# SCH_PCB_Schematic_2021-12-08.net
KiCad netlist of a schematic drawn in EasyEDA
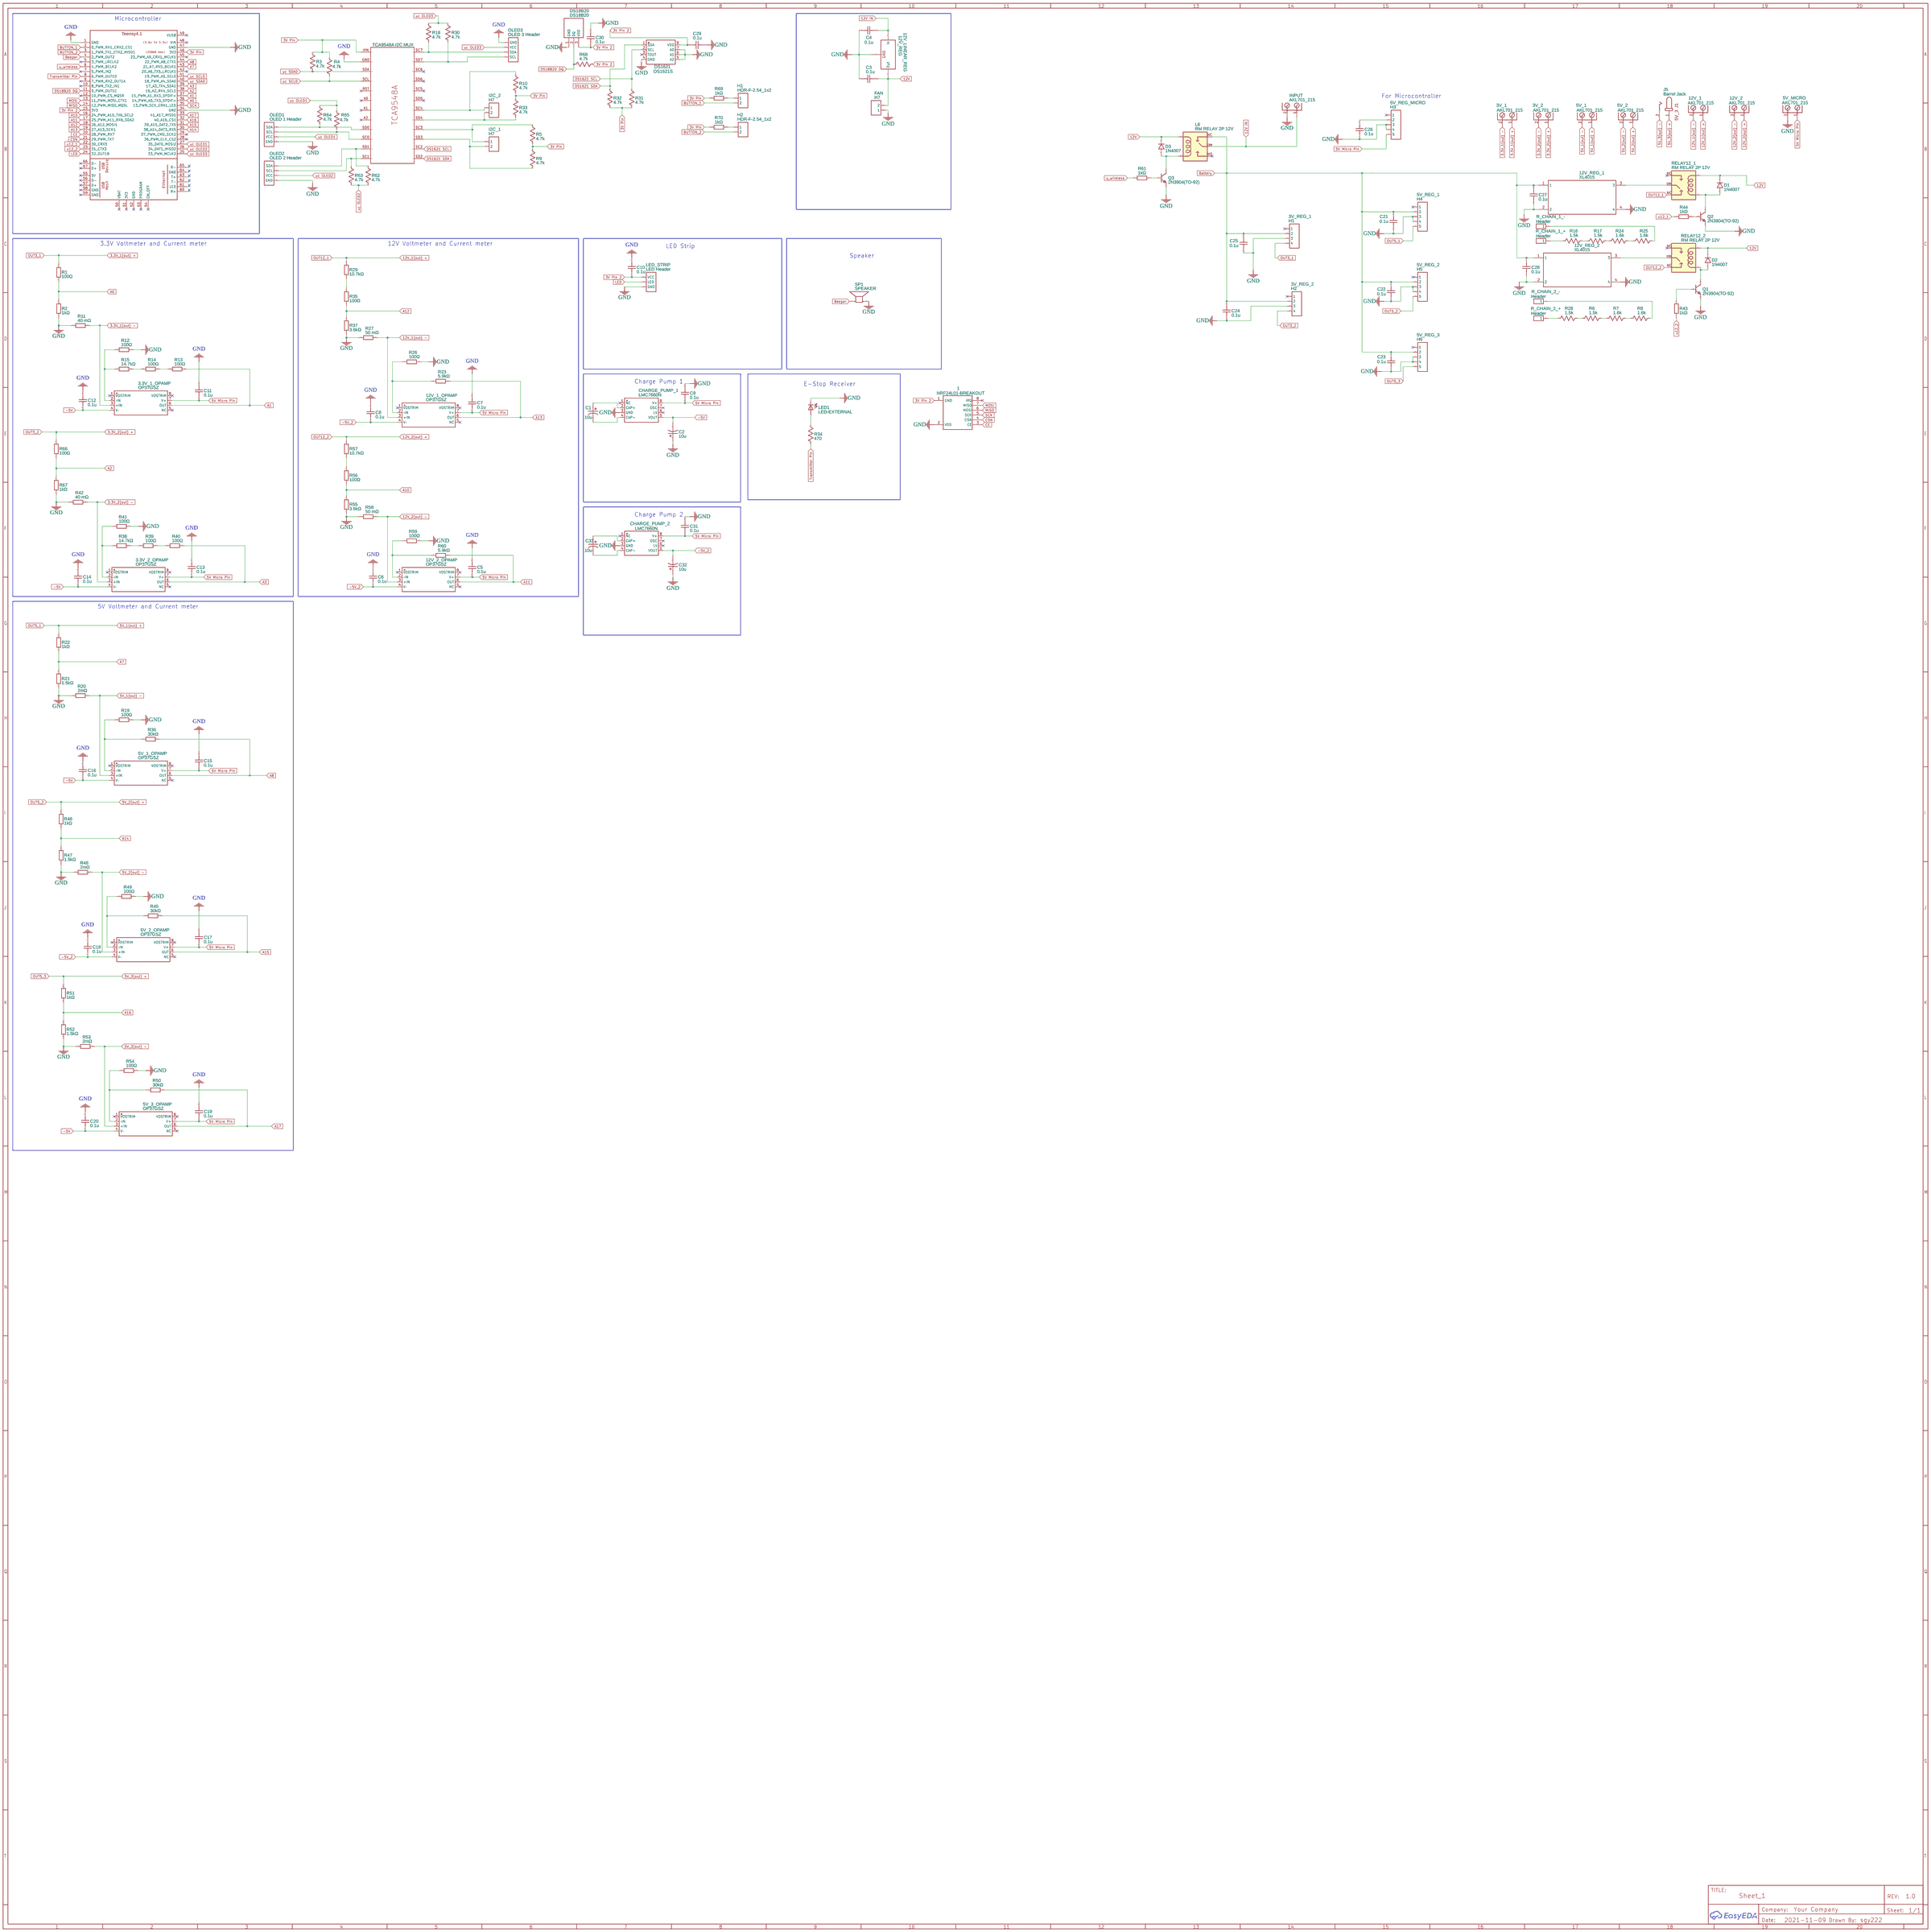
[diagram p0: schematic sheet]

(export (version "E")
  (design (tool "Eeschema 10.0.6"))
  (components
    (comp (ref "1") (value "NRF24L01-BREAKOUT") (libsource (lib "") (part "NRF24L01-BREAKOUT")))
    (comp (ref "3.3V_1_OPAMP")
      (value "OP37GSZ")
      (fields (field (name "BOM_Supplier Part") "C690944"))
      (libsource (lib "") (part "OP37GSZ_1"))
    )
    (comp (ref "3.3V_2_OPAMP")
      (value "OP37GSZ")
      (fields (field (name "BOM_Supplier Part") "C690944"))
      (libsource (lib "") (part "OP37GSZ_2"))
    )
    (comp (ref "3V_1") (value "AKL701_215") (libsource (lib "") (part "AKL701_215_1")))
    (comp (ref "3V_2") (value "AKL701_215") (libsource (lib "") (part "AKL701_215_1")))
    (comp (ref "3V_REG_1")
      (value "H1")
      (fields (field (name "BOM_Supplier Part") "C225501"))
      (libsource (lib "") (part "HDR-F-2.54_1x4"))
    )
    (comp (ref "3V_REG_2")
      (value "H2")
      (fields (field (name "BOM_Supplier Part") "C225501"))
      (libsource (lib "") (part "HDR-F-2.54_1x4"))
    )
    (comp (ref "5V_1") (value "AKL701_215") (libsource (lib "") (part "AKL701_215")))
    (comp (ref "5V_1_OPAMP")
      (value "OP37GSZ")
      (fields (field (name "BOM_Supplier Part") "C690944"))
      (libsource (lib "") (part "OP37GSZ"))
    )
    (comp (ref "5V_2") (value "AKL701_215") (libsource (lib "") (part "AKL701_215")))
    (comp (ref "5V_2_OPAMP")
      (value "OP37GSZ")
      (fields (field (name "BOM_Supplier Part") "C690944"))
      (libsource (lib "") (part "OP37GSZ_4"))
    )
    (comp (ref "5V_3_OPAMP")
      (value "OP37GSZ")
      (fields (field (name "BOM_Supplier Part") "C690944"))
      (libsource (lib "") (part "OP37GSZ_3"))
    )
    (comp (ref "5V_MICRO") (value "AKL701_215") (libsource (lib "") (part "AKL701_215_3")))
    (comp (ref "5V_REG_1")
      (value "H4")
      (fields (field (name "BOM_Supplier Part") "C50950"))
      (libsource (lib "") (part "HDR-F-2.54_1x5_1"))
    )
    (comp (ref "5V_REG_2")
      (value "H5")
      (fields (field (name "BOM_Supplier Part") "C50950"))
      (libsource (lib "") (part "HDR-F-2.54_1x5_1"))
    )
    (comp (ref "5V_REG_3")
      (value "H6")
      (fields (field (name "BOM_Supplier Part") "C50950"))
      (libsource (lib "") (part "HDR-F-2.54_1x5_1"))
    )
    (comp (ref "5V_REG_MICRO")
      (value "H3")
      (fields (field (name "BOM_Supplier Part") "C50950"))
      (libsource (lib "") (part "HDR-F-2.54_1x5"))
    )
    (comp (ref "12V_1") (value "AKL701_215") (libsource (lib "") (part "AKL701_215_2")))
    (comp (ref "12V_1_OPAMP")
      (value "OP37GSZ")
      (fields (field (name "BOM_Supplier Part") "C690944"))
      (libsource (lib "") (part "OP37GSZ_5"))
    )
    (comp (ref "12V_2") (value "AKL701_215") (libsource (lib "") (part "AKL701_215_2")))
    (comp (ref "12V_2_OPAMP")
      (value "OP37GSZ")
      (fields (field (name "BOM_Supplier Part") "C690944"))
      (libsource (lib "") (part "OP37GSZ_6"))
    )
    (comp (ref "12V_REG")
      (value "12V_LINEAR_REG")
      (fields (field (name "BOM_Manufacturer Part") "VoltageRegulator-xxV"))
      (libsource (lib "") (part "VoltageRegulator-xxV"))
    )
    (comp (ref "12V_REG_1") (value "XL4015") (libsource (lib "") (part "XL4015")))
    (comp (ref "12V_REG_2") (value "XL4015") (libsource (lib "") (part "XL4015")))
    (comp (ref "C1") (value "10u") (libsource (lib "") (part "CE_TH_D5.0×F2.0_US_2")))
    (comp (ref "C2") (value "10u") (libsource (lib "") (part "CE_TH_D5.0×F2.0_US_1")))
    (comp (ref "C3") (value "0.1u") (libsource (lib "") (part "C_0603_US_1")))
    (comp (ref "C4") (value "0.1u") (libsource (lib "") (part "C_0603_US_1")))
    (comp (ref "C5") (value "0.1u") (libsource (lib "") (part "C_0603_US")))
    (comp (ref "C6") (value "0.1u") (libsource (lib "") (part "C_0603_US_2")))
    (comp (ref "C7") (value "0.1u") (libsource (lib "") (part "C_0603_US")))
    (comp (ref "C8") (value "0.1u") (libsource (lib "") (part "C_0603_US")))
    (comp (ref "C9") (value "0.1u") (libsource (lib "") (part "C_0603_US")))
    (comp (ref "C10") (value "0.1u") (libsource (lib "") (part "C_0603_US")))
    (comp (ref "C11") (value "0.1u") (libsource (lib "") (part "C_0603_US")))
    (comp (ref "C12") (value "0.1u") (libsource (lib "") (part "C_0603_US")))
    (comp (ref "C13") (value "0.1u") (libsource (lib "") (part "C_0603_US")))
    (comp (ref "C14") (value "0.1u") (libsource (lib "") (part "C_0603_US")))
    (comp (ref "C15") (value "0.1u") (libsource (lib "") (part "C_0603_US")))
    (comp (ref "C16") (value "0.1u") (libsource (lib "") (part "C_0603_US")))
    (comp (ref "C17") (value "0.1u") (libsource (lib "") (part "C_0603_US")))
    (comp (ref "C18") (value "0.1u") (libsource (lib "") (part "C_0603_US")))
    (comp (ref "C19") (value "0.1u") (libsource (lib "") (part "C_0603_US")))
    (comp (ref "C20") (value "0.1u") (libsource (lib "") (part "C_0603_US")))
    (comp (ref "C21") (value "0.1u") (libsource (lib "") (part "C_0603_US")))
    (comp (ref "C22") (value "0.1u") (libsource (lib "") (part "C_0603_US")))
    (comp (ref "C23") (value "0.1u") (libsource (lib "") (part "C_0603_US")))
    (comp (ref "C24") (value "0.1u") (libsource (lib "") (part "C_0603_US")))
    (comp (ref "C25") (value "0.1u") (libsource (lib "") (part "C_0603_US")))
    (comp (ref "C26") (value "0.1u") (libsource (lib "") (part "C_0603_US")))
    (comp (ref "C27") (value "0.1u") (libsource (lib "") (part "C_0603_US")))
    (comp (ref "C28") (value "0.1u") (libsource (lib "") (part "C_0603_US")))
    (comp (ref "C29") (value "0.1u") (libsource (lib "") (part "C_0603_US_3")))
    (comp (ref "C30") (value "0.1u") (libsource (lib "") (part "C_0603_US_2")))
    (comp (ref "C31") (value "0.1u") (libsource (lib "") (part "C_0603_US")))
    (comp (ref "C32") (value "10u") (libsource (lib "") (part "CE_TH_D5.0×F2.0_US")))
    (comp (ref "C33") (value "10u") (libsource (lib "") (part "CE_TH_D5.0×F2.0_US_2")))
    (comp (ref "CHARGE_PUMP_1")
      (value "LMC7660N")
      (fields (field (name "BOM_Supplier Part") "C512764"))
      (libsource (lib "") (part "LMC7660N"))
    )
    (comp (ref "CHARGE_PUMP_2")
      (value "LMC7660N")
      (fields (field (name "BOM_Supplier Part") "C512764"))
      (libsource (lib "") (part "LMC7660N"))
    )
    (comp (ref "D1")
      (value "1N4007")
      (fields (field (name "BOM_Supplier Part") "C106903"))
      (libsource (lib "") (part "1N4007"))
    )
    (comp (ref "D2")
      (value "1N4007")
      (fields (field (name "BOM_Supplier Part") "C106903"))
      (libsource (lib "") (part "1N4007"))
    )
    (comp (ref "D3")
      (value "1N4007")
      (fields (field (name "BOM_Supplier Part") "C106903"))
      (libsource (lib "") (part "1N4007"))
    )
    (comp (ref "DS18B20") (value "DS18B20") (libsource (lib "") (part "DS18B20")))
    (comp (ref "DS1621")
      (value "DS1621S")
      (fields (field (name "BOM_Supplier Part") "C407894"))
      (libsource (lib "") (part "DS1621S"))
    )
    (comp (ref "FAN")
      (value "H7")
      (fields (field (name "BOM_Supplier Part") "C124375"))
      (libsource (lib "") (part "HDR-M-2.54_1x2_1"))
    )
    (comp (ref "H1")
      (value "HDR-F-2.54_1x2")
      (fields (field (name "BOM_Supplier Part") "C49661"))
      (libsource (lib "") (part "HDR-F-2.54_1x2"))
    )
    (comp (ref "H2")
      (value "HDR-F-2.54_1x2")
      (fields (field (name "BOM_Supplier Part") "C49661"))
      (libsource (lib "") (part "HDR-F-2.54_1x2"))
    )
    (comp (ref "I2C_1")
      (value "H7")
      (fields (field (name "BOM_Supplier Part") "C124375"))
      (libsource (lib "") (part "HDR-M-2.54_1x2"))
    )
    (comp (ref "I2C_2")
      (value "H7")
      (fields (field (name "BOM_Supplier Part") "C124375"))
      (libsource (lib "") (part "HDR-M-2.54_1x2"))
    )
    (comp (ref "INPUT") (value "AKL701_215") (libsource (lib "") (part "AKL701_215_4")))
    (comp (ref "J5")
      (value "Barrel Jack")
      (fields (field (name "BOM_Manufacturer Part") "PJ-037AH"))
      (libsource (lib "") (part "PJ-037AH"))
    )
    (comp (ref "L8") (value "RM RELAY 2P 12V") (libsource (lib "") (part "RM RELAY 2P 3.3V_1")))
    (comp (ref "LED1") (value "LED-EXTERNAL") (libsource (lib "") (part "LED-EXTERNAL")))
    (comp (ref "LED_STRIP")
      (value "LED Header")
      (fields (field (name "BOM_Supplier Part") "C180248"))
      (libsource (lib "") (part "HDR-M-2.54_1x3"))
    )
    (comp (ref "OLED1")
      (value "OLED 1 Header")
      (fields (field (name "BOM_Supplier Part") "C124378"))
      (libsource (lib "") (part "HDR-M-2.54_1x4"))
    )
    (comp (ref "OLED2")
      (value "OLED 2 Header")
      (fields (field (name "BOM_Supplier Part") "C124378"))
      (libsource (lib "") (part "HDR-M-2.54_1x4"))
    )
    (comp (ref "OLED3")
      (value "OLED 3 Header")
      (fields (field (name "BOM_Supplier Part") "C124378"))
      (libsource (lib "") (part "HDR-M-2.54_1x4_1"))
    )
    (comp (ref "Q1")
      (value "2N3904(TO-92)")
      (fields (field (name "BOM_Manufacturer Part") "2N3904") (field (name "BOM_Supplier Part") "C118538"))
      (libsource (lib "") (part "2N3904(TO-92)"))
    )
    (comp (ref "Q2")
      (value "2N3904(TO-92)")
      (fields (field (name "BOM_Manufacturer Part") "2N3904") (field (name "BOM_Supplier Part") "C118538"))
      (libsource (lib "") (part "2N3904(TO-92)"))
    )
    (comp (ref "Q3")
      (value "2N3904(TO-92)")
      (fields (field (name "BOM_Manufacturer Part") "2N3904") (field (name "BOM_Supplier Part") "C118538"))
      (libsource (lib "") (part "2N3904(TO-92)"))
    )
    (comp (ref "R1")
      (value "100Ω")
      (fields
        (field (name "BOM_Manufacturer Part") "AECR1206F110RK9")
        (field (name "BOM_Supplier Part") "C352159")
      )
      (libsource (lib "") (part "AECR1206F110RK9_1"))
    )
    (comp (ref "R2")
      (value "1kΩ")
      (fields
        (field (name "BOM_Manufacturer Part") "AECR1206F110RK9")
        (field (name "BOM_Supplier Part") "C352159")
      )
      (libsource (lib "") (part "AECR1206F110RK9_1"))
    )
    (comp (ref "R3") (value "4.7k") (libsource (lib "") (part "R_1206_US")))
    (comp (ref "R4") (value "4.7k") (libsource (lib "") (part "R_1206_US")))
    (comp (ref "R5") (value "4.7k") (libsource (lib "") (part "R_1206_US")))
    (comp (ref "R6") (value "1.5k") (libsource (lib "") (part "R_AXIAL-0.3_US")))
    (comp (ref "R7") (value "1.6k") (libsource (lib "") (part "R_AXIAL-0.3_US")))
    (comp (ref "R8") (value "1.6k") (libsource (lib "") (part "R_AXIAL-0.3_US")))
    (comp (ref "R9") (value "4.7k") (libsource (lib "") (part "R_1206_US_2")))
    (comp (ref "R10") (value "4.7k") (libsource (lib "") (part "R_1206_US")))
    (comp (ref "R11")
      (value "40 mΩ")
      (fields
        (field (name "BOM_Manufacturer Part") "AECR1206F110RK9")
        (field (name "BOM_Supplier Part") "C352159")
      )
      (libsource (lib "") (part "AECR1206F110RK9"))
    )
    (comp (ref "R12")
      (value "100Ω")
      (fields
        (field (name "BOM_Manufacturer Part") "AECR1206F110RK9")
        (field (name "BOM_Supplier Part") "C352159")
      )
      (libsource (lib "") (part "AECR1206F110RK9"))
    )
    (comp (ref "R13")
      (value "100Ω")
      (fields
        (field (name "BOM_Manufacturer Part") "AECR1206F110RK9")
        (field (name "BOM_Supplier Part") "C352159")
      )
      (libsource (lib "") (part "AECR1206F110RK9"))
    )
    (comp (ref "R14")
      (value "100Ω")
      (fields
        (field (name "BOM_Manufacturer Part") "AECR1206F110RK9")
        (field (name "BOM_Supplier Part") "C352159")
      )
      (libsource (lib "") (part "AECR1206F110RK9"))
    )
    (comp (ref "R15")
      (value "14.7kΩ")
      (fields
        (field (name "BOM_Manufacturer Part") "AECR1206F110RK9")
        (field (name "BOM_Supplier Part") "C352159")
      )
      (libsource (lib "") (part "AECR1206F110RK9"))
    )
    (comp (ref "R16") (value "1.5k") (libsource (lib "") (part "R_AXIAL-0.3_US")))
    (comp (ref "R17") (value "1.5k") (libsource (lib "") (part "R_AXIAL-0.3_US")))
    (comp (ref "R18") (value "4.7k") (libsource (lib "") (part "R_1206_US")))
    (comp (ref "R19")
      (value "100Ω")
      (fields
        (field (name "BOM_Manufacturer Part") "AECR1206F110RK9")
        (field (name "BOM_Supplier Part") "C352159")
      )
      (libsource (lib "") (part "AECR1206F110RK9"))
    )
    (comp (ref "R20")
      (value "2mΩ")
      (fields
        (field (name "BOM_Manufacturer Part") "AECR1206F110RK9")
        (field (name "BOM_Supplier Part") "C352159")
      )
      (libsource (lib "") (part "AECR1206F110RK9"))
    )
    (comp (ref "R21")
      (value "1.5kΩ")
      (fields
        (field (name "BOM_Manufacturer Part") "AECR1206F110RK9")
        (field (name "BOM_Supplier Part") "C352159")
      )
      (libsource (lib "") (part "AECR1206F110RK9_1"))
    )
    (comp (ref "R22")
      (value "1kΩ")
      (fields
        (field (name "BOM_Manufacturer Part") "AECR1206F110RK9")
        (field (name "BOM_Supplier Part") "C352159")
      )
      (libsource (lib "") (part "AECR1206F110RK9_1"))
    )
    (comp (ref "R23")
      (value "5.9kΩ")
      (fields
        (field (name "BOM_Manufacturer Part") "AECR1206F110RK9")
        (field (name "BOM_Supplier Part") "C352159")
      )
      (libsource (lib "") (part "AECR1206F110RK9"))
    )
    (comp (ref "R24") (value "1.6k") (libsource (lib "") (part "R_AXIAL-0.3_US")))
    (comp (ref "R25") (value "1.6k") (libsource (lib "") (part "R_AXIAL-0.3_US")))
    (comp (ref "R26")
      (value "100Ω")
      (fields
        (field (name "BOM_Manufacturer Part") "AECR1206F110RK9")
        (field (name "BOM_Supplier Part") "C352159")
      )
      (libsource (lib "") (part "AECR1206F110RK9"))
    )
    (comp (ref "R27")
      (value "50 mΩ")
      (fields
        (field (name "BOM_Manufacturer Part") "AECR1206F110RK9")
        (field (name "BOM_Supplier Part") "C352159")
      )
      (libsource (lib "") (part "AECR1206F110RK9"))
    )
    (comp (ref "R28") (value "1.5k") (libsource (lib "") (part "R_AXIAL-0.3_US")))
    (comp (ref "R29")
      (value "10.7kΩ")
      (fields
        (field (name "BOM_Manufacturer Part") "AECR1206F110RK9")
        (field (name "BOM_Supplier Part") "C352159")
      )
      (libsource (lib "") (part "AECR1206F110RK9_1"))
    )
    (comp (ref "R30") (value "4.7k") (libsource (lib "") (part "R_1206_US")))
    (comp (ref "R31") (value "4.7k") (libsource (lib "") (part "R_1206_US")))
    (comp (ref "R32") (value "4.7k") (libsource (lib "") (part "R_1206_US")))
    (comp (ref "R33") (value "4.7k") (libsource (lib "") (part "R_1206_US")))
    (comp (ref "R34") (value "470") (libsource (lib "") (part "1k 1%")))
    (comp (ref "R35")
      (value "100Ω")
      (fields
        (field (name "BOM_Manufacturer Part") "AECR1206F110RK9")
        (field (name "BOM_Supplier Part") "C352159")
      )
      (libsource (lib "") (part "AECR1206F110RK9_1"))
    )
    (comp (ref "R36")
      (value "30kΩ")
      (fields
        (field (name "BOM_Manufacturer Part") "0603WAF3022T5E")
        (field (name "BOM_Supplier Part") "C246852")
      )
      (libsource (lib "") (part "0603WAF3022T5E"))
    )
    (comp (ref "R37")
      (value "3.6kΩ")
      (fields
        (field (name "BOM_Manufacturer Part") "0603WAF3022T5E")
        (field (name "BOM_Supplier Part") "C246852")
      )
      (libsource (lib "") (part "0603WAF3022T5E_1"))
    )
    (comp (ref "R38")
      (value "14.7kΩ")
      (fields
        (field (name "BOM_Manufacturer Part") "AECR1206F110RK9")
        (field (name "BOM_Supplier Part") "C352159")
      )
      (libsource (lib "") (part "AECR1206F110RK9"))
    )
    (comp (ref "R39")
      (value "100Ω")
      (fields
        (field (name "BOM_Manufacturer Part") "AECR1206F110RK9")
        (field (name "BOM_Supplier Part") "C352159")
      )
      (libsource (lib "") (part "AECR1206F110RK9"))
    )
    (comp (ref "R40")
      (value "100Ω")
      (fields
        (field (name "BOM_Manufacturer Part") "AECR1206F110RK9")
        (field (name "BOM_Supplier Part") "C352159")
      )
      (libsource (lib "") (part "AECR1206F110RK9"))
    )
    (comp (ref "R41")
      (value "100Ω")
      (fields
        (field (name "BOM_Manufacturer Part") "AECR1206F110RK9")
        (field (name "BOM_Supplier Part") "C352159")
      )
      (libsource (lib "") (part "AECR1206F110RK9"))
    )
    (comp (ref "R42")
      (value "40 mΩ")
      (fields
        (field (name "BOM_Manufacturer Part") "AECR1206F110RK9")
        (field (name "BOM_Supplier Part") "C352159")
      )
      (libsource (lib "") (part "AECR1206F110RK9"))
    )
    (comp (ref "R43")
      (value "1kΩ")
      (fields
        (field (name "BOM_Manufacturer Part") "AECR1206F110RK9")
        (field (name "BOM_Supplier Part") "C352159")
      )
      (libsource (lib "") (part "AECR1206F110RK9_1"))
    )
    (comp (ref "R44")
      (value "1kΩ")
      (fields
        (field (name "BOM_Manufacturer Part") "AECR1206F110RK9")
        (field (name "BOM_Supplier Part") "C352159")
      )
      (libsource (lib "") (part "AECR1206F110RK9"))
    )
    (comp (ref "R45")
      (value "30kΩ")
      (fields
        (field (name "BOM_Manufacturer Part") "0603WAF3022T5E")
        (field (name "BOM_Supplier Part") "C246852")
      )
      (libsource (lib "") (part "0603WAF3022T5E"))
    )
    (comp (ref "R46")
      (value "1kΩ")
      (fields
        (field (name "BOM_Manufacturer Part") "AECR1206F110RK9")
        (field (name "BOM_Supplier Part") "C352159")
      )
      (libsource (lib "") (part "AECR1206F110RK9_1"))
    )
    (comp (ref "R47")
      (value "1.5kΩ")
      (fields
        (field (name "BOM_Manufacturer Part") "AECR1206F110RK9")
        (field (name "BOM_Supplier Part") "C352159")
      )
      (libsource (lib "") (part "AECR1206F110RK9_1"))
    )
    (comp (ref "R48")
      (value "2mΩ")
      (fields
        (field (name "BOM_Manufacturer Part") "AECR1206F110RK9")
        (field (name "BOM_Supplier Part") "C352159")
      )
      (libsource (lib "") (part "AECR1206F110RK9"))
    )
    (comp (ref "R49")
      (value "100Ω")
      (fields
        (field (name "BOM_Manufacturer Part") "AECR1206F110RK9")
        (field (name "BOM_Supplier Part") "C352159")
      )
      (libsource (lib "") (part "AECR1206F110RK9"))
    )
    (comp (ref "R50")
      (value "30kΩ")
      (fields
        (field (name "BOM_Manufacturer Part") "0603WAF3022T5E")
        (field (name "BOM_Supplier Part") "C246852")
      )
      (libsource (lib "") (part "0603WAF3022T5E"))
    )
    (comp (ref "R51")
      (value "1kΩ")
      (fields
        (field (name "BOM_Manufacturer Part") "AECR1206F110RK9")
        (field (name "BOM_Supplier Part") "C352159")
      )
      (libsource (lib "") (part "AECR1206F110RK9_1"))
    )
    (comp (ref "R52")
      (value "1.5kΩ")
      (fields
        (field (name "BOM_Manufacturer Part") "AECR1206F110RK9")
        (field (name "BOM_Supplier Part") "C352159")
      )
      (libsource (lib "") (part "AECR1206F110RK9_1"))
    )
    (comp (ref "R53")
      (value "2mΩ")
      (fields
        (field (name "BOM_Manufacturer Part") "AECR1206F110RK9")
        (field (name "BOM_Supplier Part") "C352159")
      )
      (libsource (lib "") (part "AECR1206F110RK9"))
    )
    (comp (ref "R54")
      (value "100Ω")
      (fields
        (field (name "BOM_Manufacturer Part") "AECR1206F110RK9")
        (field (name "BOM_Supplier Part") "C352159")
      )
      (libsource (lib "") (part "AECR1206F110RK9"))
    )
    (comp (ref "R55")
      (value "3.6kΩ")
      (fields
        (field (name "BOM_Manufacturer Part") "0603WAF3022T5E")
        (field (name "BOM_Supplier Part") "C246852")
      )
      (libsource (lib "") (part "0603WAF3022T5E_1"))
    )
    (comp (ref "R56")
      (value "100Ω")
      (fields
        (field (name "BOM_Manufacturer Part") "AECR1206F110RK9")
        (field (name "BOM_Supplier Part") "C352159")
      )
      (libsource (lib "") (part "AECR1206F110RK9_1"))
    )
    (comp (ref "R57")
      (value "10.7kΩ")
      (fields
        (field (name "BOM_Manufacturer Part") "AECR1206F110RK9")
        (field (name "BOM_Supplier Part") "C352159")
      )
      (libsource (lib "") (part "AECR1206F110RK9_1"))
    )
    (comp (ref "R58")
      (value "50 mΩ")
      (fields
        (field (name "BOM_Manufacturer Part") "AECR1206F110RK9")
        (field (name "BOM_Supplier Part") "C352159")
      )
      (libsource (lib "") (part "AECR1206F110RK9"))
    )
    (comp (ref "R59")
      (value "100Ω")
      (fields
        (field (name "BOM_Manufacturer Part") "AECR1206F110RK9")
        (field (name "BOM_Supplier Part") "C352159")
      )
      (libsource (lib "") (part "AECR1206F110RK9"))
    )
    (comp (ref "R60")
      (value "5.9kΩ")
      (fields
        (field (name "BOM_Manufacturer Part") "AECR1206F110RK9")
        (field (name "BOM_Supplier Part") "C352159")
      )
      (libsource (lib "") (part "AECR1206F110RK9"))
    )
    (comp (ref "R61")
      (value "1kΩ")
      (fields
        (field (name "BOM_Manufacturer Part") "AECR1206F110RK9")
        (field (name "BOM_Supplier Part") "C352159")
      )
      (libsource (lib "") (part "AECR1206F110RK9_2"))
    )
    (comp (ref "R62") (value "4.7k") (libsource (lib "") (part "R_1206_US_2")))
    (comp (ref "R63") (value "4.7k") (libsource (lib "") (part "R_1206_US")))
    (comp (ref "R64") (value "4.7k") (libsource (lib "") (part "R_1206_US")))
    (comp (ref "R65") (value "4.7k") (libsource (lib "") (part "R_1206_US")))
    (comp (ref "R66")
      (value "100Ω")
      (fields
        (field (name "BOM_Manufacturer Part") "AECR1206F110RK9")
        (field (name "BOM_Supplier Part") "C352159")
      )
      (libsource (lib "") (part "AECR1206F110RK9_1"))
    )
    (comp (ref "R67")
      (value "1kΩ")
      (fields
        (field (name "BOM_Manufacturer Part") "AECR1206F110RK9")
        (field (name "BOM_Supplier Part") "C352159")
      )
      (libsource (lib "") (part "AECR1206F110RK9_1"))
    )
    (comp (ref "R68") (value "4.7k") (libsource (lib "") (part "R_1206_US_1")))
    (comp (ref "R69")
      (value "1kΩ")
      (fields
        (field (name "BOM_Manufacturer Part") "AECR1206F110RK9")
        (field (name "BOM_Supplier Part") "C352159")
      )
      (libsource (lib "") (part "AECR1206F110RK9_2"))
    )
    (comp (ref "R70")
      (value "1kΩ")
      (fields
        (field (name "BOM_Manufacturer Part") "AECR1206F110RK9")
        (field (name "BOM_Supplier Part") "C352159")
      )
      (libsource (lib "") (part "AECR1206F110RK9_2"))
    )
    (comp (ref "RELAY12_1") (value "RM RELAY 2P 12V") (libsource (lib "") (part "RM RELAY 2P 3.3V")))
    (comp (ref "RELAY12_2") (value "RM RELAY 2P 12V") (libsource (lib "") (part "RM RELAY 2P 3.3V")))
    (comp (ref "R_CHAIN_1_+")
      (value "Header")
      (fields (field (name "BOM_Supplier Part") "C81276"))
      (libsource (lib "") (part "HDR-M-2.54_1x1_1"))
    )
    (comp (ref "R_CHAIN_1_-")
      (value "Header")
      (fields (field (name "BOM_Supplier Part") "C81276"))
      (libsource (lib "") (part "HDR-M-2.54_1x1"))
    )
    (comp (ref "R_CHAIN_2_+")
      (value "Header")
      (fields (field (name "BOM_Supplier Part") "C81276"))
      (libsource (lib "") (part "HDR-M-2.54_1x1_3"))
    )
    (comp (ref "R_CHAIN_2_-")
      (value "Header")
      (fields (field (name "BOM_Supplier Part") "C81276"))
      (libsource (lib "") (part "HDR-M-2.54_1x1_2"))
    )
    (comp (ref "SP1") (value "SPEAKER") (libsource (lib "") (part "SPEAKER")))
    (comp (ref "TEENSY")
      (value "TEENSY4.1 COMPLETE")
      (fields (field (name "BOM_Manufacturer Part") "Teensy4.1"))
      (libsource (lib "") (part "TEENSY4.1 COMPLETE"))
    )
    (comp (ref "U3")
      (value "TCA9548A I2C MUX")
      (fields (field (name "BOM_Manufacturer Part") "2717") (field (name "BOM_Supplier Part") "1528-1363-ND"))
      (libsource (lib "") (part "Adafruit TCA9548A"))
    )
  )
  (nets
    (net (code "1") (name "-5V") (class "Default")
      (node (ref "3.3V_1_OPAMP") (pin "4") (pinfunction "V–_4") (pintype "unspecified"))
      (node (ref "3.3V_2_OPAMP") (pin "4") (pinfunction "V–_4") (pintype "unspecified"))
      (node (ref "5V_1_OPAMP") (pin "4") (pinfunction "V–_4") (pintype "unspecified"))
      (node (ref "5V_3_OPAMP") (pin "4") (pinfunction "V–_4") (pintype "unspecified"))
      (node (ref "C12") (pin "1") (pinfunction "1_1") (pintype "unspecified"))
      (node (ref "C14") (pin "1") (pinfunction "1_1") (pintype "unspecified"))
      (node (ref "C16") (pin "1") (pinfunction "1_1") (pintype "unspecified"))
      (node (ref "C2") (pin "2") (pinfunction "2_2") (pintype "unspecified"))
      (node (ref "C20") (pin "1") (pinfunction "1_1") (pintype "unspecified"))
      (node (ref "CHARGE_PUMP_1") (pin "5") (pinfunction "VOUT_5") (pintype "unspecified"))
    )
    (net (code "2") (name "-5V_2") (class "Default")
      (node (ref "12V_1_OPAMP") (pin "4") (pinfunction "V–_4") (pintype "unspecified"))
      (node (ref "12V_2_OPAMP") (pin "4") (pinfunction "V–_4") (pintype "unspecified"))
      (node (ref "5V_2_OPAMP") (pin "4") (pinfunction "V–_4") (pintype "unspecified"))
      (node (ref "C18") (pin "1") (pinfunction "1_1") (pintype "unspecified"))
      (node (ref "C32") (pin "2") (pinfunction "2_2") (pintype "unspecified"))
      (node (ref "C6") (pin "2") (pinfunction "2_2") (pintype "unspecified"))
      (node (ref "C8") (pin "1") (pinfunction "1_1") (pintype "unspecified"))
      (node (ref "CHARGE_PUMP_2") (pin "5") (pinfunction "VOUT_5") (pintype "unspecified"))
    )
    (net (code "3") (name "3.3V_1(out) +") (class "Default")
      (node (ref "3V_1") (pin "1") (pinfunction "1_1") (pintype "unspecified"))
      (node (ref "3V_REG_1") (pin "4") (pinfunction "4_4") (pintype "unspecified"))
      (node (ref "R1") (pin "2") (pinfunction "2_2") (pintype "unspecified"))
    )
    (net (code "4") (name "3.3V_1(out) -") (class "Default")
      (node (ref "3.3V_1_OPAMP") (pin "3") (pinfunction "+IN_3") (pintype "unspecified"))
      (node (ref "3V_1") (pin "2") (pinfunction "2_2") (pintype "unspecified"))
      (node (ref "R11") (pin "2") (pinfunction "2_2") (pintype "unspecified"))
    )
    (net (code "5") (name "3.3V_2(out) +") (class "Default")
      (node (ref "3V_2") (pin "1") (pinfunction "1_1") (pintype "unspecified"))
      (node (ref "3V_REG_2") (pin "4") (pinfunction "4_4") (pintype "unspecified"))
      (node (ref "R66") (pin "2") (pinfunction "2_2") (pintype "unspecified"))
    )
    (net (code "6") (name "3.3V_2(out) -") (class "Default")
      (node (ref "3.3V_2_OPAMP") (pin "3") (pinfunction "+IN_3") (pintype "unspecified"))
      (node (ref "3V_2") (pin "2") (pinfunction "2_2") (pintype "unspecified"))
      (node (ref "R42") (pin "2") (pinfunction "2_2") (pintype "unspecified"))
    )
    (net (code "7") (name "3V Pin") (class "Default")
      (node (ref "R10") (pin "1") (pinfunction "1_1") (pintype "unspecified"))
      (node (ref "R3") (pin "2") (pinfunction "2_2") (pintype "unspecified"))
      (node (ref "R31") (pin "1") (pinfunction "1_1") (pintype "unspecified"))
      (node (ref "R32") (pin "1") (pinfunction "1_1") (pintype "unspecified"))
      (node (ref "R33") (pin "2") (pinfunction "2_2") (pintype "unspecified"))
      (node (ref "R4") (pin "2") (pinfunction "2_2") (pintype "unspecified"))
      (node (ref "R5") (pin "1") (pinfunction "1_1") (pintype "unspecified"))
      (node (ref "R69") (pin "2") (pinfunction "2_2") (pintype "unspecified"))
      (node (ref "R70") (pin "2") (pinfunction "2_2") (pintype "unspecified"))
      (node (ref "R9") (pin "1") (pinfunction "1_1") (pintype "unspecified"))
      (node (ref "TEENSY") (pin "46") (pinfunction "3V3_46") (pintype "bidirectional"))
      (node (ref "U3") (pin "VIN") (pinfunction "VIN_VIN") (pintype "unspecified"))
    )
    (net (code "8") (name "3V Pin 2") (class "Default")
      (node (ref "1") (pin "1") (pinfunction "GND_1") (pintype "bidirectional"))
      (node (ref "C10") (pin "1") (pinfunction "1_1") (pintype "unspecified"))
      (node (ref "C29") (pin "2") (pinfunction "2_2") (pintype "unspecified"))
      (node (ref "C30") (pin "2") (pinfunction "2_2") (pintype "unspecified"))
      (node (ref "DS1621") (pin "8") (pinfunction "VDD_8") (pintype "unspecified"))
      (node (ref "DS18B20") (pin "3") (pinfunction "VDD_3") (pintype "unspecified"))
      (node (ref "LED_STRIP") (pin "1") (pinfunction "VCC_1") (pintype "input"))
      (node (ref "R68") (pin "1") (pinfunction "1_1") (pintype "unspecified"))
      (node (ref "TEENSY") (pin "15") (pinfunction "3V3_15") (pintype "bidirectional"))
    )
    (net (code "9") (name "5V Micro Pin") (class "Default")
      (node (ref "12V_1_OPAMP") (pin "7") (pinfunction "V+_7") (pintype "unspecified"))
      (node (ref "12V_2_OPAMP") (pin "7") (pinfunction "V+_7") (pintype "unspecified"))
      (node (ref "3.3V_1_OPAMP") (pin "7") (pinfunction "V+_7") (pintype "unspecified"))
      (node (ref "3.3V_2_OPAMP") (pin "7") (pinfunction "V+_7") (pintype "unspecified"))
      (node (ref "5V_1_OPAMP") (pin "7") (pinfunction "V+_7") (pintype "unspecified"))
      (node (ref "5V_2_OPAMP") (pin "7") (pinfunction "V+_7") (pintype "unspecified"))
      (node (ref "5V_3_OPAMP") (pin "7") (pinfunction "V+_7") (pintype "unspecified"))
      (node (ref "5V_MICRO") (pin "1") (pinfunction "1_1") (pintype "unspecified"))
      (node (ref "5V_REG_MICRO") (pin "5") (pinfunction "5_5") (pintype "unspecified"))
      (node (ref "C11") (pin "1") (pinfunction "1_1") (pintype "unspecified"))
      (node (ref "C13") (pin "1") (pinfunction "1_1") (pintype "unspecified"))
      (node (ref "C15") (pin "1") (pinfunction "1_1") (pintype "unspecified"))
      (node (ref "C17") (pin "1") (pinfunction "1_1") (pintype "unspecified"))
      (node (ref "C19") (pin "1") (pinfunction "1_1") (pintype "unspecified"))
      (node (ref "C31") (pin "1") (pinfunction "1_1") (pintype "unspecified"))
      (node (ref "C5") (pin "1") (pinfunction "1_1") (pintype "unspecified"))
      (node (ref "C7") (pin "1") (pinfunction "1_1") (pintype "unspecified"))
      (node (ref "C9") (pin "1") (pinfunction "1_1") (pintype "unspecified"))
      (node (ref "CHARGE_PUMP_1") (pin "8") (pinfunction "V+_8") (pintype "unspecified"))
      (node (ref "CHARGE_PUMP_2") (pin "8") (pinfunction "V+_8") (pintype "unspecified"))
    )
    (net (code "10") (name "5V_1(out) +") (class "Default")
      (node (ref "5V_1") (pin "1") (pinfunction "1_1") (pintype "unspecified"))
      (node (ref "5V_REG_1") (pin "5") (pinfunction "5_5") (pintype "unspecified"))
      (node (ref "R22") (pin "2") (pinfunction "2_2") (pintype "unspecified"))
    )
    (net (code "11") (name "5V_1(out) -") (class "Default")
      (node (ref "5V_1") (pin "2") (pinfunction "2_2") (pintype "unspecified"))
      (node (ref "5V_1_OPAMP") (pin "3") (pinfunction "+IN_3") (pintype "unspecified"))
      (node (ref "R20") (pin "2") (pinfunction "2_2") (pintype "unspecified"))
    )
    (net (code "12") (name "5V_2(out) +") (class "Default")
      (node (ref "5V_2") (pin "1") (pinfunction "1_1") (pintype "unspecified"))
      (node (ref "5V_REG_2") (pin "5") (pinfunction "5_5") (pintype "unspecified"))
      (node (ref "R46") (pin "2") (pinfunction "2_2") (pintype "unspecified"))
    )
    (net (code "13") (name "5V_2(out) -") (class "Default")
      (node (ref "5V_2") (pin "2") (pinfunction "2_2") (pintype "unspecified"))
      (node (ref "5V_2_OPAMP") (pin "3") (pinfunction "+IN_3") (pintype "unspecified"))
      (node (ref "R48") (pin "2") (pinfunction "2_2") (pintype "unspecified"))
    )
    (net (code "14") (name "5V_3(out) +") (class "Default")
      (node (ref "5V_REG_3") (pin "5") (pinfunction "5_5") (pintype "unspecified"))
      (node (ref "J5") (pin "1") (pinfunction "1_1") (pintype "bidirectional"))
      (node (ref "R51") (pin "2") (pinfunction "2_2") (pintype "unspecified"))
    )
    (net (code "15") (name "5V_3(out) -") (class "Default")
      (node (ref "5V_3_OPAMP") (pin "3") (pinfunction "+IN_3") (pintype "unspecified"))
      (node (ref "J5") (pin "2") (pinfunction "2_2") (pintype "bidirectional"))
      (node (ref "R53") (pin "2") (pinfunction "2_2") (pintype "unspecified"))
    )
    (net (code "16") (name "12V") (class "Default")
      (node (ref "12V_REG") (pin "3") (pinfunction "Out_3") (pintype "unspecified"))
      (node (ref "C3") (pin "2") (pinfunction "2_2") (pintype "unspecified"))
      (node (ref "D1") (pin "1") (pinfunction "1_1") (pintype "unspecified"))
      (node (ref "D2") (pin "1") (pinfunction "1_1") (pintype "unspecified"))
      (node (ref "D3") (pin "1") (pinfunction "1_1") (pintype "unspecified"))
      (node (ref "FAN") (pin "2") (pinfunction "2_2") (pintype "unspecified"))
      (node (ref "L8") (pin "COIL1") (pinfunction "COIL1_COIL1") (pintype "unspecified"))
      (node (ref "RELAY12_1") (pin "COIL2") (pinfunction "COIL2_COIL2") (pintype "unspecified"))
      (node (ref "RELAY12_2") (pin "COIL2") (pinfunction "COIL2_COIL2") (pintype "unspecified"))
    )
    (net (code "17") (name "12V IN") (class "Default")
      (node (ref "12V_REG") (pin "1") (pinfunction "In_1") (pintype "unspecified"))
      (node (ref "C4") (pin "2") (pinfunction "2_2") (pintype "unspecified"))
      (node (ref "INPUT") (pin "1") (pinfunction "1_1") (pintype "unspecified"))
      (node (ref "L8") (pin "COM") (pinfunction "COM_COM") (pintype "unspecified"))
    )
    (net (code "18") (name "12V_1(out) +") (class "Default")
      (node (ref "12V_1") (pin "1") (pinfunction "1_1") (pintype "unspecified"))
      (node (ref "R29") (pin "2") (pinfunction "2_2") (pintype "unspecified"))
      (node (ref "RELAY12_1") (pin "NC") (pinfunction "NC_NC") (pintype "unspecified"))
    )
    (net (code "19") (name "12V_1(out) -") (class "Default")
      (node (ref "12V_1") (pin "2") (pinfunction "2_2") (pintype "unspecified"))
      (node (ref "12V_1_OPAMP") (pin "3") (pinfunction "+IN_3") (pintype "unspecified"))
      (node (ref "R27") (pin "2") (pinfunction "2_2") (pintype "unspecified"))
    )
    (net (code "20") (name "12V_2(out) +") (class "Default")
      (node (ref "12V_2") (pin "1") (pinfunction "1_1") (pintype "unspecified"))
      (node (ref "R57") (pin "2") (pinfunction "2_2") (pintype "unspecified"))
      (node (ref "RELAY12_2") (pin "NC") (pinfunction "NC_NC") (pintype "unspecified"))
    )
    (net (code "21") (name "12V_2(out) -") (class "Default")
      (node (ref "12V_2") (pin "2") (pinfunction "2_2") (pintype "unspecified"))
      (node (ref "12V_2_OPAMP") (pin "3") (pinfunction "+IN_3") (pintype "unspecified"))
      (node (ref "R58") (pin "2") (pinfunction "2_2") (pintype "unspecified"))
    )
    (net (code "22") (name "A0") (class "Default")
      (node (ref "R1") (pin "1") (pinfunction "1_1") (pintype "unspecified"))
      (node (ref "R2") (pin "2") (pinfunction "2_2") (pintype "unspecified"))
      (node (ref "TEENSY") (pin "36") (pinfunction "14_PWM_A0_TX3_SPDIF>_36") (pintype "bidirectional"))
    )
    (net (code "23") (name "A1") (class "Default")
      (node (ref "3.3V_1_OPAMP") (pin "6") (pinfunction "OUT_6") (pintype "unspecified"))
      (node (ref "R13") (pin "2") (pinfunction "2_2") (pintype "unspecified"))
      (node (ref "TEENSY") (pin "37") (pinfunction "15_PWM_A1_RX3_SPDIF<_37") (pintype "bidirectional"))
    )
    (net (code "24") (name "A2") (class "Default")
      (node (ref "R66") (pin "1") (pinfunction "1_1") (pintype "unspecified"))
      (node (ref "R67") (pin "2") (pinfunction "2_2") (pintype "unspecified"))
      (node (ref "TEENSY") (pin "38") (pinfunction "16_A2_RX4_SCL1_38") (pintype "bidirectional"))
    )
    (net (code "25") (name "A3") (class "Default")
      (node (ref "3.3V_2_OPAMP") (pin "6") (pinfunction "OUT_6") (pintype "unspecified"))
      (node (ref "R40") (pin "2") (pinfunction "2_2") (pintype "unspecified"))
      (node (ref "TEENSY") (pin "39") (pinfunction "17_A3_TX4_SDA1_39") (pintype "bidirectional"))
    )
    (net (code "26") (name "A7") (class "Default")
      (node (ref "R21") (pin "2") (pinfunction "2_2") (pintype "unspecified"))
      (node (ref "R22") (pin "1") (pinfunction "1_1") (pintype "unspecified"))
      (node (ref "TEENSY") (pin "43") (pinfunction "21_A7_RX5_BCLK1_43") (pintype "bidirectional"))
    )
    (net (code "27") (name "A8") (class "Default")
      (node (ref "5V_1_OPAMP") (pin "6") (pinfunction "OUT_6") (pintype "unspecified"))
      (node (ref "R36") (pin "2") (pinfunction "2_2") (pintype "unspecified"))
      (node (ref "TEENSY") (pin "44") (pinfunction "22_PWM_A8_CTX1_44") (pintype "bidirectional"))
    )
    (net (code "28") (name "A10") (class "Default")
      (node (ref "R55") (pin "2") (pinfunction "2_2") (pintype "unspecified"))
      (node (ref "R56") (pin "1") (pinfunction "1_1") (pintype "unspecified"))
      (node (ref "TEENSY") (pin "16") (pinfunction "24_PWM_A10_TX6_SCL2_16") (pintype "bidirectional"))
    )
    (net (code "29") (name "A11") (class "Default")
      (node (ref "12V_2_OPAMP") (pin "6") (pinfunction "OUT_6") (pintype "unspecified"))
      (node (ref "R60") (pin "2") (pinfunction "2_2") (pintype "unspecified"))
      (node (ref "TEENSY") (pin "17") (pinfunction "25_PWM_A11_RX6_SDA2_17") (pintype "bidirectional"))
    )
    (net (code "30") (name "A12") (class "Default")
      (node (ref "R35") (pin "1") (pinfunction "1_1") (pintype "unspecified"))
      (node (ref "R37") (pin "2") (pinfunction "2_2") (pintype "unspecified"))
      (node (ref "TEENSY") (pin "18") (pinfunction "26_A12_MOSI1_18") (pintype "bidirectional"))
    )
    (net (code "31") (name "A13") (class "Default")
      (node (ref "12V_1_OPAMP") (pin "6") (pinfunction "OUT_6") (pintype "unspecified"))
      (node (ref "R23") (pin "2") (pinfunction "2_2") (pintype "unspecified"))
      (node (ref "TEENSY") (pin "19") (pinfunction "27_A13_SCK1_19") (pintype "bidirectional"))
    )
    (net (code "32") (name "A14") (class "Default")
      (node (ref "R46") (pin "1") (pinfunction "1_1") (pintype "unspecified"))
      (node (ref "R47") (pin "2") (pinfunction "2_2") (pintype "unspecified"))
      (node (ref "TEENSY") (pin "30") (pinfunction "38_A14_DAT3_RX5_30") (pintype "bidirectional"))
    )
    (net (code "33") (name "A15") (class "Default")
      (node (ref "5V_2_OPAMP") (pin "6") (pinfunction "OUT_6") (pintype "unspecified"))
      (node (ref "R45") (pin "2") (pinfunction "2_2") (pintype "unspecified"))
      (node (ref "TEENSY") (pin "31") (pinfunction "39_A15_DAT2_TX5_31") (pintype "bidirectional"))
    )
    (net (code "34") (name "A16") (class "Default")
      (node (ref "R51") (pin "1") (pinfunction "1_1") (pintype "unspecified"))
      (node (ref "R52") (pin "2") (pinfunction "2_2") (pintype "unspecified"))
      (node (ref "TEENSY") (pin "32") (pinfunction "40_A16_CS1_32") (pintype "bidirectional"))
    )
    (net (code "35") (name "A17") (class "Default")
      (node (ref "5V_3_OPAMP") (pin "6") (pinfunction "OUT_6") (pintype "unspecified"))
      (node (ref "R50") (pin "2") (pinfunction "2_2") (pintype "unspecified"))
      (node (ref "TEENSY") (pin "33") (pinfunction "41_A17_MIS01_33") (pintype "bidirectional"))
    )
    (net (code "36") (name "BUTTON_1") (class "Default")
      (node (ref "H1") (pin "2") (pinfunction "2_2") (pintype "input"))
      (node (ref "TEENSY") (pin "2") (pinfunction "0_PWM_RX1_CRX2_CS1_2") (pintype "bidirectional"))
    )
    (net (code "37") (name "BUTTON_2") (class "Default")
      (node (ref "H2") (pin "2") (pinfunction "2_2") (pintype "input"))
      (node (ref "TEENSY") (pin "3") (pinfunction "1_PWM_TX1_CTX2_MISO1_3") (pintype "bidirectional"))
    )
    (net (code "38") (name "Battery") (class "Default")
      (node (ref "12V_REG_1") (pin "1") (pinfunction "1_1") (pintype "unspecified"))
      (node (ref "12V_REG_2") (pin "1") (pinfunction "1_1") (pintype "unspecified"))
      (node (ref "3V_REG_1") (pin "2") (pinfunction "2_2") (pintype "unspecified"))
      (node (ref "3V_REG_2") (pin "2") (pinfunction "2_2") (pintype "unspecified"))
      (node (ref "5V_REG_1") (pin "2") (pinfunction "2_2") (pintype "unspecified"))
      (node (ref "5V_REG_2") (pin "2") (pinfunction "2_2") (pintype "unspecified"))
      (node (ref "5V_REG_3") (pin "2") (pinfunction "2_2") (pintype "unspecified"))
      (node (ref "C21") (pin "2") (pinfunction "2_2") (pintype "unspecified"))
      (node (ref "C22") (pin "2") (pinfunction "2_2") (pintype "unspecified"))
      (node (ref "C23") (pin "2") (pinfunction "2_2") (pintype "unspecified"))
      (node (ref "C24") (pin "2") (pinfunction "2_2") (pintype "unspecified"))
      (node (ref "C25") (pin "2") (pinfunction "2_2") (pintype "unspecified"))
      (node (ref "C27") (pin "2") (pinfunction "2_2") (pintype "unspecified"))
      (node (ref "C28") (pin "2") (pinfunction "2_2") (pintype "unspecified"))
      (node (ref "L8") (pin "NC") (pinfunction "NC_NC") (pintype "unspecified"))
    )
    (net (code "39") (name "Beeper") (class "Default")
      (node (ref "SP1") (pin "1") (pinfunction "+_1") (pintype "unspecified"))
      (node (ref "TEENSY") (pin "4") (pinfunction "2_PWM_OUT2_4") (pintype "bidirectional"))
    )
    (net (code "40") (name "CE") (class "Default")
      (node (ref "1") (pin "3") (pinfunction "CE_3") (pintype "bidirectional"))
      (node (ref "TEENSY") (pin "20") (pinfunction "28_PWM_RX7_20") (pintype "bidirectional"))
    )
    (net (code "41") (name "CSN") (class "Default")
      (node (ref "1") (pin "4") (pinfunction "CSN_4") (pintype "bidirectional"))
      (node (ref "TEENSY") (pin "21") (pinfunction "29_PWM_TX7_21") (pintype "bidirectional"))
    )
    (net (code "42") (name "DS18B20 DQ") (class "Default")
      (node (ref "DS18B20") (pin "2") (pinfunction "DQ_2") (pintype "unspecified"))
      (node (ref "R68") (pin "2") (pinfunction "2_2") (pintype "unspecified"))
      (node (ref "TEENSY") (pin "11") (pinfunction "9_PWM_OUT1C_11") (pintype "bidirectional"))
    )
    (net (code "43") (name "DS1621 SCL") (class "Default")
      (node (ref "DS1621") (pin "2") (pinfunction "SCL_2") (pintype "unspecified"))
      (node (ref "R31") (pin "2") (pinfunction "2_2") (pintype "unspecified"))
      (node (ref "U3") (pin "SC2") (pinfunction "SC2_SC2") (pintype "unspecified"))
    )
    (net (code "44") (name "DS1621 SDA") (class "Default")
      (node (ref "DS1621") (pin "1") (pinfunction "SDA_1") (pintype "unspecified"))
      (node (ref "R32") (pin "2") (pinfunction "2_2") (pintype "unspecified"))
      (node (ref "U3") (pin "SD2") (pinfunction "SD2_SD2") (pintype "unspecified"))
    )
    (net (code "45") (name "GND") (class "Default")
      (node (ref "1") (pin "2") (pinfunction "VDD_2") (pintype "bidirectional"))
      (node (ref "12V_REG") (pin "2") (pinfunction "GND_2") (pintype "unspecified"))
      (node (ref "12V_REG_1") (pin "2") (pinfunction "2_2") (pintype "unspecified"))
      (node (ref "12V_REG_1") (pin "4") (pinfunction "4_4") (pintype "unspecified"))
      (node (ref "12V_REG_2") (pin "2") (pinfunction "2_2") (pintype "unspecified"))
      (node (ref "12V_REG_2") (pin "4") (pinfunction "4_4") (pintype "unspecified"))
      (node (ref "3V_REG_1") (pin "3") (pinfunction "3_3") (pintype "unspecified"))
      (node (ref "3V_REG_2") (pin "3") (pinfunction "3_3") (pintype "unspecified"))
      (node (ref "5V_MICRO") (pin "2") (pinfunction "2_2") (pintype "unspecified"))
      (node (ref "5V_REG_1") (pin "3") (pinfunction "3_3") (pintype "unspecified"))
      (node (ref "5V_REG_1") (pin "4") (pinfunction "4_4") (pintype "unspecified"))
      (node (ref "5V_REG_2") (pin "3") (pinfunction "3_3") (pintype "unspecified"))
      (node (ref "5V_REG_2") (pin "4") (pinfunction "4_4") (pintype "unspecified"))
      (node (ref "5V_REG_3") (pin "3") (pinfunction "3_3") (pintype "unspecified"))
      (node (ref "5V_REG_3") (pin "4") (pinfunction "4_4") (pintype "unspecified"))
      (node (ref "5V_REG_MICRO") (pin "3") (pinfunction "3_3") (pintype "unspecified"))
      (node (ref "5V_REG_MICRO") (pin "4") (pinfunction "4_4") (pintype "unspecified"))
      (node (ref "C10") (pin "2") (pinfunction "2_2") (pintype "unspecified"))
      (node (ref "C11") (pin "2") (pinfunction "2_2") (pintype "unspecified"))
      (node (ref "C12") (pin "2") (pinfunction "2_2") (pintype "unspecified"))
      (node (ref "C13") (pin "2") (pinfunction "2_2") (pintype "unspecified"))
      (node (ref "C14") (pin "2") (pinfunction "2_2") (pintype "unspecified"))
      (node (ref "C15") (pin "2") (pinfunction "2_2") (pintype "unspecified"))
      (node (ref "C16") (pin "2") (pinfunction "2_2") (pintype "unspecified"))
      (node (ref "C17") (pin "2") (pinfunction "2_2") (pintype "unspecified"))
      (node (ref "C18") (pin "2") (pinfunction "2_2") (pintype "unspecified"))
      (node (ref "C19") (pin "2") (pinfunction "2_2") (pintype "unspecified"))
      (node (ref "C2") (pin "1") (pinfunction "1_1") (pintype "unspecified"))
      (node (ref "C20") (pin "2") (pinfunction "2_2") (pintype "unspecified"))
      (node (ref "C21") (pin "1") (pinfunction "1_1") (pintype "unspecified"))
      (node (ref "C22") (pin "1") (pinfunction "1_1") (pintype "unspecified"))
      (node (ref "C23") (pin "1") (pinfunction "1_1") (pintype "unspecified"))
      (node (ref "C24") (pin "1") (pinfunction "1_1") (pintype "unspecified"))
      (node (ref "C25") (pin "1") (pinfunction "1_1") (pintype "unspecified"))
      (node (ref "C26") (pin "1") (pinfunction "1_1") (pintype "unspecified"))
      (node (ref "C27") (pin "1") (pinfunction "1_1") (pintype "unspecified"))
      (node (ref "C28") (pin "1") (pinfunction "1_1") (pintype "unspecified"))
      (node (ref "C29") (pin "1") (pinfunction "1_1") (pintype "unspecified"))
      (node (ref "C3") (pin "1") (pinfunction "1_1") (pintype "unspecified"))
      (node (ref "C30") (pin "1") (pinfunction "1_1") (pintype "unspecified"))
      (node (ref "C31") (pin "2") (pinfunction "2_2") (pintype "unspecified"))
      (node (ref "C32") (pin "1") (pinfunction "1_1") (pintype "unspecified"))
      (node (ref "C4") (pin "1") (pinfunction "1_1") (pintype "unspecified"))
      (node (ref "C5") (pin "2") (pinfunction "2_2") (pintype "unspecified"))
      (node (ref "C6") (pin "1") (pinfunction "1_1") (pintype "unspecified"))
      (node (ref "C7") (pin "2") (pinfunction "2_2") (pintype "unspecified"))
      (node (ref "C8") (pin "2") (pinfunction "2_2") (pintype "unspecified"))
      (node (ref "C9") (pin "2") (pinfunction "2_2") (pintype "unspecified"))
      (node (ref "CHARGE_PUMP_1") (pin "3") (pinfunction "GND_3") (pintype "unspecified"))
      (node (ref "CHARGE_PUMP_2") (pin "3") (pinfunction "GND_3") (pintype "unspecified"))
      (node (ref "DS1621") (pin "4") (pinfunction "GND_4") (pintype "unspecified"))
      (node (ref "DS1621") (pin "5") (pinfunction "A2_5") (pintype "unspecified"))
      (node (ref "DS1621") (pin "6") (pinfunction "A1_6") (pintype "unspecified"))
      (node (ref "DS1621") (pin "7") (pinfunction "A0_7") (pintype "unspecified"))
      (node (ref "DS18B20") (pin "1") (pinfunction "GND_1") (pintype "unspecified"))
      (node (ref "FAN") (pin "1") (pinfunction "1_1") (pintype "unspecified"))
      (node (ref "INPUT") (pin "2") (pinfunction "2_2") (pintype "unspecified"))
      (node (ref "LED1") (pin "2") (pinfunction "K_2") (pintype "bidirectional"))
      (node (ref "LED_STRIP") (pin "3") (pinfunction "GND_3") (pintype "input"))
      (node (ref "OLED1") (pin "1") (pinfunction "GND_1") (pintype "unspecified"))
      (node (ref "OLED2") (pin "1") (pinfunction "GND_1") (pintype "unspecified"))
      (node (ref "OLED3") (pin "1") (pinfunction "GND_1") (pintype "unspecified"))
      (node (ref "Q1") (pin "1") (pinfunction "E_1") (pintype "unspecified"))
      (node (ref "Q2") (pin "1") (pinfunction "E_1") (pintype "unspecified"))
      (node (ref "Q3") (pin "1") (pinfunction "E_1") (pintype "unspecified"))
      (node (ref "R11") (pin "1") (pinfunction "1_1") (pintype "unspecified"))
      (node (ref "R12") (pin "2") (pinfunction "2_2") (pintype "unspecified"))
      (node (ref "R19") (pin "2") (pinfunction "2_2") (pintype "unspecified"))
      (node (ref "R2") (pin "1") (pinfunction "1_1") (pintype "unspecified"))
      (node (ref "R20") (pin "1") (pinfunction "1_1") (pintype "unspecified"))
      (node (ref "R21") (pin "1") (pinfunction "1_1") (pintype "unspecified"))
      (node (ref "R26") (pin "2") (pinfunction "2_2") (pintype "unspecified"))
      (node (ref "R27") (pin "1") (pinfunction "1_1") (pintype "unspecified"))
      (node (ref "R37") (pin "1") (pinfunction "1_1") (pintype "unspecified"))
      (node (ref "R41") (pin "2") (pinfunction "2_2") (pintype "unspecified"))
      (node (ref "R42") (pin "1") (pinfunction "1_1") (pintype "unspecified"))
      (node (ref "R47") (pin "1") (pinfunction "1_1") (pintype "unspecified"))
      (node (ref "R48") (pin "1") (pinfunction "1_1") (pintype "unspecified"))
      (node (ref "R49") (pin "2") (pinfunction "2_2") (pintype "unspecified"))
      (node (ref "R52") (pin "1") (pinfunction "1_1") (pintype "unspecified"))
      (node (ref "R53") (pin "1") (pinfunction "1_1") (pintype "unspecified"))
      (node (ref "R54") (pin "2") (pinfunction "2_2") (pintype "unspecified"))
      (node (ref "R55") (pin "1") (pinfunction "1_1") (pintype "unspecified"))
      (node (ref "R58") (pin "1") (pinfunction "1_1") (pintype "unspecified"))
      (node (ref "R59") (pin "2") (pinfunction "2_2") (pintype "unspecified"))
      (node (ref "R67") (pin "1") (pinfunction "1_1") (pintype "unspecified"))
      (node (ref "SP1") (pin "2") (pinfunction "-_2") (pintype "unspecified"))
      (node (ref "TEENSY") (pin "1") (pinfunction "GND_1") (pintype "bidirectional"))
      (node (ref "TEENSY") (pin "34") (pinfunction "GND_34") (pintype "bidirectional"))
      (node (ref "TEENSY") (pin "47") (pinfunction "GND_47") (pintype "bidirectional"))
      (node (ref "U3") (pin "GND") (pinfunction "GND_GND") (pintype "unspecified"))
    )
    (net (code "46") (name "LED") (class "Default")
      (node (ref "LED_STRIP") (pin "2") (pinfunction "LED_2") (pintype "input"))
      (node (ref "TEENSY") (pin "24") (pinfunction "32_OUT1B_24") (pintype "bidirectional"))
    )
    (net (code "47") (name "MISO") (class "Default")
      (node (ref "1") (pin "6") (pinfunction "MOSI_6") (pintype "bidirectional"))
      (node (ref "TEENSY") (pin "14") (pinfunction "12_PWM_MISO_MQSL_14") (pintype "bidirectional"))
    )
    (net (code "48") (name "MOSI") (class "Default")
      (node (ref "1") (pin "7") (pinfunction "MISO_7") (pintype "bidirectional"))
      (node (ref "TEENSY") (pin "13") (pinfunction "11_PWM_MOSI_CTX1_13") (pintype "bidirectional"))
    )
    (net (code "49") (name "Net-(3.3V_1_OPAMP-–IN)") (class "Default")
      (node (ref "3.3V_1_OPAMP") (pin "2") (pinfunction "–IN_2") (pintype "unspecified"))
      (node (ref "R12") (pin "1") (pinfunction "1_1") (pintype "unspecified"))
      (node (ref "R15") (pin "1") (pinfunction "1_1") (pintype "unspecified"))
    )
    (net (code "50") (name "Net-(3.3V_2_OPAMP-–IN)") (class "Default")
      (node (ref "3.3V_2_OPAMP") (pin "2") (pinfunction "–IN_2") (pintype "unspecified"))
      (node (ref "R38") (pin "1") (pinfunction "1_1") (pintype "unspecified"))
      (node (ref "R41") (pin "1") (pinfunction "1_1") (pintype "unspecified"))
    )
    (net (code "51") (name "Net-(5V_1_OPAMP-–IN)") (class "Default")
      (node (ref "5V_1_OPAMP") (pin "2") (pinfunction "–IN_2") (pintype "unspecified"))
      (node (ref "R19") (pin "1") (pinfunction "1_1") (pintype "unspecified"))
      (node (ref "R36") (pin "1") (pinfunction "1_1") (pintype "unspecified"))
    )
    (net (code "52") (name "Net-(5V_2_OPAMP-–IN)") (class "Default")
      (node (ref "5V_2_OPAMP") (pin "2") (pinfunction "–IN_2") (pintype "unspecified"))
      (node (ref "R45") (pin "1") (pinfunction "1_1") (pintype "unspecified"))
      (node (ref "R49") (pin "1") (pinfunction "1_1") (pintype "unspecified"))
    )
    (net (code "53") (name "Net-(5V_3_OPAMP-–IN)") (class "Default")
      (node (ref "5V_3_OPAMP") (pin "2") (pinfunction "–IN_2") (pintype "unspecified"))
      (node (ref "R50") (pin "1") (pinfunction "1_1") (pintype "unspecified"))
      (node (ref "R54") (pin "1") (pinfunction "1_1") (pintype "unspecified"))
    )
    (net (code "54") (name "Net-(5V_REG_MICRO-Pad2)") (class "Default")
      (node (ref "5V_REG_MICRO") (pin "2") (pinfunction "2_2") (pintype "unspecified"))
      (node (ref "C26") (pin "2") (pinfunction "2_2") (pintype "unspecified"))
    )
    (net (code "55") (name "Net-(12V_1_OPAMP-–IN)") (class "Default")
      (node (ref "12V_1_OPAMP") (pin "2") (pinfunction "–IN_2") (pintype "unspecified"))
      (node (ref "R23") (pin "1") (pinfunction "1_1") (pintype "unspecified"))
      (node (ref "R26") (pin "1") (pinfunction "1_1") (pintype "unspecified"))
    )
    (net (code "56") (name "Net-(12V_2_OPAMP-–IN)") (class "Default")
      (node (ref "12V_2_OPAMP") (pin "2") (pinfunction "–IN_2") (pintype "unspecified"))
      (node (ref "R59") (pin "1") (pinfunction "1_1") (pintype "unspecified"))
      (node (ref "R60") (pin "1") (pinfunction "1_1") (pintype "unspecified"))
    )
    (net (code "57") (name "Net-(12V_REG_1-Pad3)") (class "Default")
      (node (ref "12V_REG_1") (pin "3") (pinfunction "3_3") (pintype "unspecified"))
      (node (ref "RELAY12_1") (pin "COM") (pinfunction "COM_COM") (pintype "unspecified"))
    )
    (net (code "58") (name "Net-(12V_REG_2-Pad3)") (class "Default")
      (node (ref "12V_REG_2") (pin "3") (pinfunction "3_3") (pintype "unspecified"))
      (node (ref "RELAY12_2") (pin "COM") (pinfunction "COM_COM") (pintype "unspecified"))
    )
    (net (code "59") (name "Net-(CHARGE_PUMP_1-CAP+)") (class "Default")
      (node (ref "C1") (pin "1") (pinfunction "1_1") (pintype "unspecified"))
      (node (ref "CHARGE_PUMP_1") (pin "2") (pinfunction "CAP+_2") (pintype "unspecified"))
    )
    (net (code "60") (name "Net-(CHARGE_PUMP_1-CAP-)") (class "Default")
      (node (ref "C1") (pin "2") (pinfunction "2_2") (pintype "unspecified"))
      (node (ref "CHARGE_PUMP_1") (pin "4") (pinfunction "CAP-_4") (pintype "unspecified"))
    )
    (net (code "61") (name "Net-(CHARGE_PUMP_2-CAP+)") (class "Default")
      (node (ref "C33") (pin "1") (pinfunction "1_1") (pintype "unspecified"))
      (node (ref "CHARGE_PUMP_2") (pin "2") (pinfunction "CAP+_2") (pintype "unspecified"))
    )
    (net (code "62") (name "Net-(CHARGE_PUMP_2-CAP-)") (class "Default")
      (node (ref "C33") (pin "2") (pinfunction "2_2") (pintype "unspecified"))
      (node (ref "CHARGE_PUMP_2") (pin "4") (pinfunction "CAP-_4") (pintype "unspecified"))
    )
    (net (code "63") (name "Net-(H1-Pad1)") (class "Default")
      (node (ref "H1") (pin "1") (pinfunction "1_1") (pintype "input"))
      (node (ref "R69") (pin "1") (pinfunction "1_1") (pintype "unspecified"))
    )
    (net (code "64") (name "Net-(H2-Pad1)") (class "Default")
      (node (ref "H2") (pin "1") (pinfunction "1_1") (pintype "input"))
      (node (ref "R70") (pin "1") (pinfunction "1_1") (pintype "unspecified"))
    )
    (net (code "65") (name "Net-(I2C_1-Pad1)") (class "Default")
      (node (ref "I2C_1") (pin "1") (pinfunction "1_1") (pintype "unspecified"))
      (node (ref "R5") (pin "2") (pinfunction "2_2") (pintype "unspecified"))
      (node (ref "U3") (pin "SC3") (pinfunction "SC3_SC3") (pintype "unspecified"))
    )
    (net (code "66") (name "Net-(I2C_1-Pad2)") (class "Default")
      (node (ref "I2C_1") (pin "2") (pinfunction "2_2") (pintype "unspecified"))
      (node (ref "R9") (pin "2") (pinfunction "2_2") (pintype "unspecified"))
      (node (ref "U3") (pin "SD3") (pinfunction "SD3_SD3") (pintype "unspecified"))
    )
    (net (code "67") (name "Net-(I2C_2-Pad1)") (class "Default")
      (node (ref "I2C_2") (pin "1") (pinfunction "1_1") (pintype "unspecified"))
      (node (ref "R10") (pin "2") (pinfunction "2_2") (pintype "unspecified"))
      (node (ref "U3") (pin "SC4") (pinfunction "SC4_SC4") (pintype "unspecified"))
    )
    (net (code "68") (name "Net-(I2C_2-Pad2)") (class "Default")
      (node (ref "I2C_2") (pin "2") (pinfunction "2_2") (pintype "unspecified"))
      (node (ref "R33") (pin "1") (pinfunction "1_1") (pintype "unspecified"))
      (node (ref "U3") (pin "SD4") (pinfunction "SD4_SD4") (pintype "unspecified"))
    )
    (net (code "69") (name "Net-(LED1-A)") (class "Default")
      (node (ref "LED1") (pin "1") (pinfunction "A_1") (pintype "bidirectional"))
      (node (ref "R34") (pin "2") (pinfunction "2_2") (pintype "unspecified"))
    )
    (net (code "70") (name "Net-(OLED1-SCL)") (class "Default")
      (node (ref "OLED1") (pin "3") (pinfunction "SCL_3") (pintype "unspecified"))
      (node (ref "R65") (pin "1") (pinfunction "1_1") (pintype "unspecified"))
      (node (ref "U3") (pin "SC0") (pinfunction "SC0_SC0") (pintype "unspecified"))
    )
    (net (code "71") (name "Net-(OLED1-SDA)") (class "Default")
      (node (ref "OLED1") (pin "4") (pinfunction "SDA_4") (pintype "unspecified"))
      (node (ref "R64") (pin "1") (pinfunction "1_1") (pintype "unspecified"))
      (node (ref "U3") (pin "SD0") (pinfunction "SD0_SD0") (pintype "unspecified"))
    )
    (net (code "72") (name "Net-(OLED2-SCL)") (class "Default")
      (node (ref "OLED2") (pin "3") (pinfunction "SCL_3") (pintype "unspecified"))
      (node (ref "R63") (pin "2") (pinfunction "2_2") (pintype "unspecified"))
      (node (ref "U3") (pin "SC1") (pinfunction "SC1_SC1") (pintype "unspecified"))
    )
    (net (code "73") (name "Net-(OLED2-SDA)") (class "Default")
      (node (ref "OLED2") (pin "4") (pinfunction "SDA_4") (pintype "unspecified"))
      (node (ref "R62") (pin "1") (pinfunction "1_1") (pintype "unspecified"))
      (node (ref "U3") (pin "SD1") (pinfunction "SD1_SD1") (pintype "unspecified"))
    )
    (net (code "74") (name "Net-(OLED3-SCL)") (class "Default")
      (node (ref "OLED3") (pin "4") (pinfunction "SCL_4") (pintype "unspecified"))
      (node (ref "R30") (pin "1") (pinfunction "1_1") (pintype "unspecified"))
      (node (ref "U3") (pin "SD7") (pinfunction "SD7_SD7") (pintype "unspecified"))
    )
    (net (code "75") (name "Net-(OLED3-SDA)") (class "Default")
      (node (ref "OLED3") (pin "3") (pinfunction "SDA_3") (pintype "unspecified"))
      (node (ref "R18") (pin "1") (pinfunction "1_1") (pintype "unspecified"))
      (node (ref "U3") (pin "SC7") (pinfunction "SC7_SC7") (pintype "unspecified"))
    )
    (net (code "76") (name "Net-(Q1-B)") (class "Default")
      (node (ref "Q1") (pin "2") (pinfunction "B_2") (pintype "unspecified"))
      (node (ref "R43") (pin "2") (pinfunction "2_2") (pintype "unspecified"))
    )
    (net (code "77") (name "Net-(Q1-C)") (class "Default")
      (node (ref "D2") (pin "2") (pinfunction "2_2") (pintype "unspecified"))
      (node (ref "Q1") (pin "3") (pinfunction "C_3") (pintype "unspecified"))
      (node (ref "RELAY12_2") (pin "COIL1") (pinfunction "COIL1_COIL1") (pintype "unspecified"))
    )
    (net (code "78") (name "Net-(Q2-B)") (class "Default")
      (node (ref "Q2") (pin "2") (pinfunction "B_2") (pintype "unspecified"))
      (node (ref "R44") (pin "2") (pinfunction "2_2") (pintype "unspecified"))
    )
    (net (code "79") (name "Net-(Q2-C)") (class "Default")
      (node (ref "D1") (pin "2") (pinfunction "2_2") (pintype "unspecified"))
      (node (ref "Q2") (pin "3") (pinfunction "C_3") (pintype "unspecified"))
      (node (ref "RELAY12_1") (pin "COIL1") (pinfunction "COIL1_COIL1") (pintype "unspecified"))
    )
    (net (code "80") (name "Net-(Q3-B)") (class "Default")
      (node (ref "Q3") (pin "2") (pinfunction "B_2") (pintype "unspecified"))
      (node (ref "R61") (pin "1") (pinfunction "1_1") (pintype "unspecified"))
    )
    (net (code "81") (name "Net-(Q3-C)") (class "Default")
      (node (ref "D3") (pin "2") (pinfunction "2_2") (pintype "unspecified"))
      (node (ref "L8") (pin "COIL2") (pinfunction "COIL2_COIL2") (pintype "unspecified"))
      (node (ref "Q3") (pin "3") (pinfunction "C_3") (pintype "unspecified"))
    )
    (net (code "82") (name "Net-(R6-Pad2)") (class "Default")
      (node (ref "R6") (pin "2") (pinfunction "2_2") (pintype "unspecified"))
      (node (ref "R7") (pin "1") (pinfunction "1_1") (pintype "unspecified"))
    )
    (net (code "83") (name "Net-(R7-Pad2)") (class "Default")
      (node (ref "R7") (pin "2") (pinfunction "2_2") (pintype "unspecified"))
      (node (ref "R8") (pin "1") (pinfunction "1_1") (pintype "unspecified"))
    )
    (net (code "84") (name "Net-(R8-Pad2)") (class "Default")
      (node (ref "R8") (pin "2") (pinfunction "2_2") (pintype "unspecified"))
      (node (ref "R_CHAIN_2_-") (pin "1") (pinfunction "1_1") (pintype "input"))
    )
    (net (code "85") (name "Net-(R13-Pad1)") (class "Default")
      (node (ref "R13") (pin "1") (pinfunction "1_1") (pintype "unspecified"))
      (node (ref "R14") (pin "2") (pinfunction "2_2") (pintype "unspecified"))
    )
    (net (code "86") (name "Net-(R14-Pad1)") (class "Default")
      (node (ref "R14") (pin "1") (pinfunction "1_1") (pintype "unspecified"))
      (node (ref "R15") (pin "2") (pinfunction "2_2") (pintype "unspecified"))
    )
    (net (code "87") (name "Net-(R16-Pad1)") (class "Default")
      (node (ref "R16") (pin "1") (pinfunction "1_1") (pintype "unspecified"))
      (node (ref "R_CHAIN_1_+") (pin "1") (pinfunction "1_1") (pintype "input"))
    )
    (net (code "88") (name "Net-(R16-Pad2)") (class "Default")
      (node (ref "R16") (pin "2") (pinfunction "2_2") (pintype "unspecified"))
      (node (ref "R17") (pin "1") (pinfunction "1_1") (pintype "unspecified"))
    )
    (net (code "89") (name "Net-(R17-Pad2)") (class "Default")
      (node (ref "R17") (pin "2") (pinfunction "2_2") (pintype "unspecified"))
      (node (ref "R24") (pin "1") (pinfunction "1_1") (pintype "unspecified"))
    )
    (net (code "90") (name "Net-(R24-Pad2)") (class "Default")
      (node (ref "R24") (pin "2") (pinfunction "2_2") (pintype "unspecified"))
      (node (ref "R25") (pin "1") (pinfunction "1_1") (pintype "unspecified"))
    )
    (net (code "91") (name "Net-(R25-Pad2)") (class "Default")
      (node (ref "R25") (pin "2") (pinfunction "2_2") (pintype "unspecified"))
      (node (ref "R_CHAIN_1_-") (pin "1") (pinfunction "1_1") (pintype "input"))
    )
    (net (code "92") (name "Net-(R28-Pad1)") (class "Default")
      (node (ref "R28") (pin "1") (pinfunction "1_1") (pintype "unspecified"))
      (node (ref "R_CHAIN_2_+") (pin "1") (pinfunction "1_1") (pintype "input"))
    )
    (net (code "93") (name "Net-(R28-Pad2)") (class "Default")
      (node (ref "R28") (pin "2") (pinfunction "2_2") (pintype "unspecified"))
      (node (ref "R6") (pin "1") (pinfunction "1_1") (pintype "unspecified"))
    )
    (net (code "94") (name "Net-(R29-Pad1)") (class "Default")
      (node (ref "R29") (pin "1") (pinfunction "1_1") (pintype "unspecified"))
      (node (ref "R35") (pin "2") (pinfunction "2_2") (pintype "unspecified"))
    )
    (net (code "95") (name "Net-(R38-Pad2)") (class "Default")
      (node (ref "R38") (pin "2") (pinfunction "2_2") (pintype "unspecified"))
      (node (ref "R39") (pin "1") (pinfunction "1_1") (pintype "unspecified"))
    )
    (net (code "96") (name "Net-(R39-Pad2)") (class "Default")
      (node (ref "R39") (pin "2") (pinfunction "2_2") (pintype "unspecified"))
      (node (ref "R40") (pin "1") (pinfunction "1_1") (pintype "unspecified"))
    )
    (net (code "97") (name "Net-(R56-Pad2)") (class "Default")
      (node (ref "R56") (pin "2") (pinfunction "2_2") (pintype "unspecified"))
      (node (ref "R57") (pin "1") (pinfunction "1_1") (pintype "unspecified"))
    )
    (net (code "98") (name "SCK") (class "Default")
      (node (ref "1") (pin "5") (pinfunction "SCK_5") (pintype "bidirectional"))
      (node (ref "TEENSY") (pin "35") (pinfunction "13_PWM_SCK_CRX1_LED_35") (pintype "bidirectional"))
    )
    (net (code "99") (name "Transmitter Pin") (class "Default")
      (node (ref "R34") (pin "1") (pinfunction "1_1") (pintype "unspecified"))
      (node (ref "TEENSY") (pin "8") (pinfunction "6_PWM_OUT1D_8") (pintype "bidirectional"))
    )
    (net (code "100") (name "u12_1") (class "Default")
      (node (ref "R44") (pin "1") (pinfunction "1_1") (pintype "unspecified"))
      (node (ref "TEENSY") (pin "22") (pinfunction "30_CRX3_22") (pintype "bidirectional"))
    )
    (net (code "101") (name "u12_2") (class "Default")
      (node (ref "R43") (pin "1") (pinfunction "1_1") (pintype "unspecified"))
      (node (ref "TEENSY") (pin "23") (pinfunction "31_CTX3_23") (pintype "bidirectional"))
    )
    (net (code "102") (name "u_wireless") (class "Default")
      (node (ref "R61") (pin "2") (pinfunction "2_2") (pintype "unspecified"))
      (node (ref "TEENSY") (pin "6") (pinfunction "4_PWM_BCLK2_6") (pintype "bidirectional"))
    )
    (net (code "103") (name "uc OLED1") (class "Default")
      (node (ref "OLED1") (pin "2") (pinfunction "VCC_2") (pintype "unspecified"))
      (node (ref "R64") (pin "2") (pinfunction "2_2") (pintype "unspecified"))
      (node (ref "R65") (pin "2") (pinfunction "2_2") (pintype "unspecified"))
      (node (ref "TEENSY") (pin "27") (pinfunction "35_DAT0_MOSI2_27") (pintype "bidirectional"))
    )
    (net (code "104") (name "uc OLED2") (class "Default")
      (node (ref "OLED2") (pin "2") (pinfunction "VCC_2") (pintype "unspecified"))
      (node (ref "R62") (pin "2") (pinfunction "2_2") (pintype "unspecified"))
      (node (ref "R63") (pin "1") (pinfunction "1_1") (pintype "unspecified"))
      (node (ref "TEENSY") (pin "26") (pinfunction "34_DAT1_MISO2_26") (pintype "bidirectional"))
    )
    (net (code "105") (name "uc OLED3") (class "Default")
      (node (ref "OLED3") (pin "2") (pinfunction "VCC_2") (pintype "unspecified"))
      (node (ref "R18") (pin "2") (pinfunction "2_2") (pintype "unspecified"))
      (node (ref "R30") (pin "2") (pinfunction "2_2") (pintype "unspecified"))
      (node (ref "TEENSY") (pin "25") (pinfunction "33_PWM_MCLK2_25") (pintype "bidirectional"))
    )
    (net (code "106") (name "uc SCL0") (class "Default")
      (node (ref "R4") (pin "1") (pinfunction "1_1") (pintype "unspecified"))
      (node (ref "TEENSY") (pin "41") (pinfunction "19_PWM_A5_SCL0_41") (pintype "bidirectional"))
      (node (ref "U3") (pin "SCL") (pinfunction "SCL_SCL") (pintype "unspecified"))
    )
    (net (code "107") (name "uc SDA0") (class "Default")
      (node (ref "R3") (pin "1") (pinfunction "1_1") (pintype "unspecified"))
      (node (ref "TEENSY") (pin "40") (pinfunction "18_PWM_A4_SDA0_40") (pintype "bidirectional"))
      (node (ref "U3") (pin "SDA") (pinfunction "SDA_SDA") (pintype "unspecified"))
    )
    (net (code "108") (name "unconnected-(1-IRQ-Pad8)") (class "Default")
      (node (ref "1") (pin "8") (pinfunction "IRQ_8") (pintype "bidirectional+no_connect"))
    )
    (net (code "109") (name "unconnected-(3.3V_1_OPAMP-NC-Pad5)") (class "Default")
      (node (ref "3.3V_1_OPAMP") (pin "5") (pinfunction "NC_5") (pintype "unspecified+no_connect"))
    )
    (net (code "110") (name "unconnected-(3.3V_1_OPAMP-VOSTRIM-Pad1)") (class "Default")
      (node (ref "3.3V_1_OPAMP") (pin "1") (pinfunction "VOSTRIM_1") (pintype "unspecified+no_connect"))
    )
    (net (code "111") (name "unconnected-(3.3V_1_OPAMP-VOSTRIM-Pad8)") (class "Default")
      (node (ref "3.3V_1_OPAMP") (pin "8") (pinfunction "VOSTRIM_8") (pintype "unspecified+no_connect"))
    )
    (net (code "112") (name "unconnected-(3.3V_2_OPAMP-NC-Pad5)") (class "Default")
      (node (ref "3.3V_2_OPAMP") (pin "5") (pinfunction "NC_5") (pintype "unspecified+no_connect"))
    )
    (net (code "113") (name "unconnected-(3.3V_2_OPAMP-VOSTRIM-Pad1)") (class "Default")
      (node (ref "3.3V_2_OPAMP") (pin "1") (pinfunction "VOSTRIM_1") (pintype "unspecified+no_connect"))
    )
    (net (code "114") (name "unconnected-(3.3V_2_OPAMP-VOSTRIM-Pad8)") (class "Default")
      (node (ref "3.3V_2_OPAMP") (pin "8") (pinfunction "VOSTRIM_8") (pintype "unspecified+no_connect"))
    )
    (net (code "115") (name "unconnected-(3V_REG_1-Pad1)") (class "Default")
      (node (ref "3V_REG_1") (pin "1") (pinfunction "1_1") (pintype "unspecified+no_connect"))
    )
    (net (code "116") (name "unconnected-(3V_REG_2-Pad1)") (class "Default")
      (node (ref "3V_REG_2") (pin "1") (pinfunction "1_1") (pintype "unspecified+no_connect"))
    )
    (net (code "117") (name "unconnected-(5V_1_OPAMP-NC-Pad5)") (class "Default")
      (node (ref "5V_1_OPAMP") (pin "5") (pinfunction "NC_5") (pintype "unspecified+no_connect"))
    )
    (net (code "118") (name "unconnected-(5V_1_OPAMP-VOSTRIM-Pad1)") (class "Default")
      (node (ref "5V_1_OPAMP") (pin "1") (pinfunction "VOSTRIM_1") (pintype "unspecified+no_connect"))
    )
    (net (code "119") (name "unconnected-(5V_1_OPAMP-VOSTRIM-Pad8)") (class "Default")
      (node (ref "5V_1_OPAMP") (pin "8") (pinfunction "VOSTRIM_8") (pintype "unspecified+no_connect"))
    )
    (net (code "120") (name "unconnected-(5V_2_OPAMP-NC-Pad5)") (class "Default")
      (node (ref "5V_2_OPAMP") (pin "5") (pinfunction "NC_5") (pintype "unspecified+no_connect"))
    )
    (net (code "121") (name "unconnected-(5V_2_OPAMP-VOSTRIM-Pad1)") (class "Default")
      (node (ref "5V_2_OPAMP") (pin "1") (pinfunction "VOSTRIM_1") (pintype "unspecified+no_connect"))
    )
    (net (code "122") (name "unconnected-(5V_2_OPAMP-VOSTRIM-Pad8)") (class "Default")
      (node (ref "5V_2_OPAMP") (pin "8") (pinfunction "VOSTRIM_8") (pintype "unspecified+no_connect"))
    )
    (net (code "123") (name "unconnected-(5V_3_OPAMP-NC-Pad5)") (class "Default")
      (node (ref "5V_3_OPAMP") (pin "5") (pinfunction "NC_5") (pintype "unspecified+no_connect"))
    )
    (net (code "124") (name "unconnected-(5V_3_OPAMP-VOSTRIM-Pad1)") (class "Default")
      (node (ref "5V_3_OPAMP") (pin "1") (pinfunction "VOSTRIM_1") (pintype "unspecified+no_connect"))
    )
    (net (code "125") (name "unconnected-(5V_3_OPAMP-VOSTRIM-Pad8)") (class "Default")
      (node (ref "5V_3_OPAMP") (pin "8") (pinfunction "VOSTRIM_8") (pintype "unspecified+no_connect"))
    )
    (net (code "126") (name "unconnected-(5V_REG_1-Pad1)") (class "Default")
      (node (ref "5V_REG_1") (pin "1") (pinfunction "1_1") (pintype "unspecified+no_connect"))
    )
    (net (code "127") (name "unconnected-(5V_REG_2-Pad1)") (class "Default")
      (node (ref "5V_REG_2") (pin "1") (pinfunction "1_1") (pintype "unspecified+no_connect"))
    )
    (net (code "128") (name "unconnected-(5V_REG_3-Pad1)") (class "Default")
      (node (ref "5V_REG_3") (pin "1") (pinfunction "1_1") (pintype "unspecified+no_connect"))
    )
    (net (code "129") (name "unconnected-(5V_REG_MICRO-Pad1)") (class "Default")
      (node (ref "5V_REG_MICRO") (pin "1") (pinfunction "1_1") (pintype "unspecified+no_connect"))
    )
    (net (code "130") (name "unconnected-(12V_1_OPAMP-NC-Pad5)") (class "Default")
      (node (ref "12V_1_OPAMP") (pin "5") (pinfunction "NC_5") (pintype "unspecified+no_connect"))
    )
    (net (code "131") (name "unconnected-(12V_1_OPAMP-VOSTRIM-Pad1)") (class "Default")
      (node (ref "12V_1_OPAMP") (pin "1") (pinfunction "VOSTRIM_1") (pintype "unspecified+no_connect"))
    )
    (net (code "132") (name "unconnected-(12V_1_OPAMP-VOSTRIM-Pad8)") (class "Default")
      (node (ref "12V_1_OPAMP") (pin "8") (pinfunction "VOSTRIM_8") (pintype "unspecified+no_connect"))
    )
    (net (code "133") (name "unconnected-(12V_2_OPAMP-NC-Pad5)") (class "Default")
      (node (ref "12V_2_OPAMP") (pin "5") (pinfunction "NC_5") (pintype "unspecified+no_connect"))
    )
    (net (code "134") (name "unconnected-(12V_2_OPAMP-VOSTRIM-Pad1)") (class "Default")
      (node (ref "12V_2_OPAMP") (pin "1") (pinfunction "VOSTRIM_1") (pintype "unspecified+no_connect"))
    )
    (net (code "135") (name "unconnected-(12V_2_OPAMP-VOSTRIM-Pad8)") (class "Default")
      (node (ref "12V_2_OPAMP") (pin "8") (pinfunction "VOSTRIM_8") (pintype "unspecified+no_connect"))
    )
    (net (code "136") (name "unconnected-(CHARGE_PUMP_1-LV-Pad6)") (class "Default")
      (node (ref "CHARGE_PUMP_1") (pin "6") (pinfunction "LV_6") (pintype "unspecified+no_connect"))
    )
    (net (code "137") (name "unconnected-(CHARGE_PUMP_1-NC-Pad1)") (class "Default")
      (node (ref "CHARGE_PUMP_1") (pin "1") (pinfunction "NC_1") (pintype "unspecified+no_connect"))
    )
    (net (code "138") (name "unconnected-(CHARGE_PUMP_1-OSC-Pad7)") (class "Default")
      (node (ref "CHARGE_PUMP_1") (pin "7") (pinfunction "OSC_7") (pintype "unspecified+no_connect"))
    )
    (net (code "139") (name "unconnected-(CHARGE_PUMP_2-LV-Pad6)") (class "Default")
      (node (ref "CHARGE_PUMP_2") (pin "6") (pinfunction "LV_6") (pintype "unspecified+no_connect"))
    )
    (net (code "140") (name "unconnected-(CHARGE_PUMP_2-NC-Pad1)") (class "Default")
      (node (ref "CHARGE_PUMP_2") (pin "1") (pinfunction "NC_1") (pintype "unspecified+no_connect"))
    )
    (net (code "141") (name "unconnected-(CHARGE_PUMP_2-OSC-Pad7)") (class "Default")
      (node (ref "CHARGE_PUMP_2") (pin "7") (pinfunction "OSC_7") (pintype "unspecified+no_connect"))
    )
    (net (code "142") (name "unconnected-(DS1621-TOUT-Pad3)") (class "Default")
      (node (ref "DS1621") (pin "3") (pinfunction "TOUT_3") (pintype "unspecified+no_connect"))
    )
    (net (code "143") (name "unconnected-(L8-PadNO)") (class "Default")
      (node (ref "L8") (pin "NO") (pinfunction "NO_NO") (pintype "unspecified+no_connect"))
    )
    (net (code "144") (name "unconnected-(RELAY12_1-PadNO)") (class "Default")
      (node (ref "RELAY12_1") (pin "NO") (pinfunction "NO_NO") (pintype "unspecified+no_connect"))
    )
    (net (code "145") (name "unconnected-(RELAY12_2-PadNO)") (class "Default")
      (node (ref "RELAY12_2") (pin "NO") (pinfunction "NO_NO") (pintype "unspecified+no_connect"))
    )
    (net (code "146") (name "unconnected-(TEENSY-3V3-Pad51)") (class "Default")
      (node (ref "TEENSY") (pin "51") (pinfunction "3V3_51") (pintype "bidirectional+no_connect"))
    )
    (net (code "147") (name "unconnected-(TEENSY-3_PWM_LRCLK2-Pad5)") (class "Default")
      (node (ref "TEENSY") (pin "5") (pinfunction "3_PWM_LRCLK2_5") (pintype "bidirectional+no_connect"))
    )
    (net (code "148") (name "unconnected-(TEENSY-5V-Pad55)") (class "Default")
      (node (ref "TEENSY") (pin "55") (pinfunction "5V_55") (pintype "bidirectional+no_connect"))
    )
    (net (code "149") (name "unconnected-(TEENSY-5_PWM_IN2-Pad7)") (class "Default")
      (node (ref "TEENSY") (pin "7") (pinfunction "5_PWM_IN2_7") (pintype "bidirectional+no_connect"))
    )
    (net (code "150") (name "unconnected-(TEENSY-7_PWM_RX2_OUT1A-Pad9)") (class "Default")
      (node (ref "TEENSY") (pin "9") (pinfunction "7_PWM_RX2_OUT1A_9") (pintype "bidirectional+no_connect"))
    )
    (net (code "151") (name "unconnected-(TEENSY-8_PWM_TX2_IN1-Pad10)") (class "Default")
      (node (ref "TEENSY") (pin "10") (pinfunction "8_PWM_TX2_IN1_10") (pintype "bidirectional+no_connect"))
    )
    (net (code "152") (name "unconnected-(TEENSY-10_PWM_CS_MQSR-Pad12)") (class "Default")
      (node (ref "TEENSY") (pin "12") (pinfunction "10_PWM_CS_MQSR_12") (pintype "bidirectional+no_connect"))
    )
    (net (code "153") (name "unconnected-(TEENSY-20_A6_TX5_LRCLK1-Pad42)") (class "Default")
      (node (ref "TEENSY") (pin "42") (pinfunction "20_A6_TX5_LRCLK1_42") (pintype "bidirectional+no_connect"))
    )
    (net (code "154") (name "unconnected-(TEENSY-23_PWM_A9_CRX1_MCLK1-Pad45)") (class "Default")
      (node (ref "TEENSY") (pin "45") (pinfunction "23_PWM_A9_CRX1_MCLK1_45") (pintype "bidirectional+no_connect"))
    )
    (net (code "155") (name "unconnected-(TEENSY-36_PWM_CLK_CS2-Pad28)") (class "Default")
      (node (ref "TEENSY") (pin "28") (pinfunction "36_PWM_CLK_CS2_28") (pintype "bidirectional+no_connect"))
    )
    (net (code "156") (name "unconnected-(TEENSY-37_PWM_CMD_SCK2-Pad29)") (class "Default")
      (node (ref "TEENSY") (pin "29") (pinfunction "37_PWM_CMD_SCK2_29") (pintype "bidirectional+no_connect"))
    )
    (net (code "157") (name "unconnected-(TEENSY-D+-Pad57)") (class "Default")
      (node (ref "TEENSY") (pin "57") (pinfunction "D+_57") (pintype "bidirectional+no_connect"))
    )
    (net (code "158") (name "unconnected-(TEENSY-D+-Pad67)") (class "Default")
      (node (ref "TEENSY") (pin "67") (pinfunction "D+_67") (pintype "bidirectional+no_connect"))
    )
    (net (code "159") (name "unconnected-(TEENSY-D--Pad56)") (class "Default")
      (node (ref "TEENSY") (pin "56") (pinfunction "D-_56") (pintype "bidirectional+no_connect"))
    )
    (net (code "160") (name "unconnected-(TEENSY-D--Pad66)") (class "Default")
      (node (ref "TEENSY") (pin "66") (pinfunction "D-_66") (pintype "bidirectional+no_connect"))
    )
    (net (code "161") (name "unconnected-(TEENSY-GND-Pad52)") (class "Default")
      (node (ref "TEENSY") (pin "52") (pinfunction "GND_52") (pintype "bidirectional+no_connect"))
    )
    (net (code "162") (name "unconnected-(TEENSY-GND-Pad58)") (class "Default")
      (node (ref "TEENSY") (pin "58") (pinfunction "GND_58") (pintype "bidirectional+no_connect"))
    )
    (net (code "163") (name "unconnected-(TEENSY-GND-Pad59)") (class "Default")
      (node (ref "TEENSY") (pin "59") (pinfunction "GND_59") (pintype "bidirectional+no_connect"))
    )
    (net (code "164") (name "unconnected-(TEENSY-GND-Pad64)") (class "Default")
      (node (ref "TEENSY") (pin "64") (pinfunction "GND_64") (pintype "bidirectional+no_connect"))
    )
    (net (code "165") (name "unconnected-(TEENSY-LED-Pad61)") (class "Default")
      (node (ref "TEENSY") (pin "61") (pinfunction "LED_61") (pintype "bidirectional+no_connect"))
    )
    (net (code "166") (name "unconnected-(TEENSY-ON_OFF-Pad54)") (class "Default")
      (node (ref "TEENSY") (pin "54") (pinfunction "ON_OFF_54") (pintype "input+no_connect"))
    )
    (net (code "167") (name "unconnected-(TEENSY-PROGRAM-Pad53)") (class "Default")
      (node (ref "TEENSY") (pin "53") (pinfunction "PROGRAM_53") (pintype "input+no_connect"))
    )
    (net (code "168") (name "unconnected-(TEENSY-R+-Pad60)") (class "Default")
      (node (ref "TEENSY") (pin "60") (pinfunction "R+_60") (pintype "bidirectional+no_connect"))
    )
    (net (code "169") (name "unconnected-(TEENSY-R--Pad65)") (class "Default")
      (node (ref "TEENSY") (pin "65") (pinfunction "R-_65") (pintype "bidirectional+no_connect"))
    )
    (net (code "170") (name "unconnected-(TEENSY-T+-Pad63)") (class "Default")
      (node (ref "TEENSY") (pin "63") (pinfunction "T+_63") (pintype "bidirectional+no_connect"))
    )
    (net (code "171") (name "unconnected-(TEENSY-T--Pad62)") (class "Default")
      (node (ref "TEENSY") (pin "62") (pinfunction "T-_62") (pintype "bidirectional+no_connect"))
    )
    (net (code "172") (name "unconnected-(TEENSY-VBAT-Pad50)") (class "Default")
      (node (ref "TEENSY") (pin "50") (pinfunction "VBAT_50") (pintype "bidirectional+no_connect"))
    )
    (net (code "173") (name "unconnected-(TEENSY-VIN-Pad48)") (class "Default")
      (node (ref "TEENSY") (pin "48") (pinfunction "VIN_48") (pintype "bidirectional+no_connect"))
    )
    (net (code "174") (name "unconnected-(TEENSY-VUSB-Pad49)") (class "Default")
      (node (ref "TEENSY") (pin "49") (pinfunction "VUSB_49") (pintype "bidirectional+no_connect"))
    )
    (net (code "175") (name "unconnected-(U3-PadA0)") (class "Default")
      (node (ref "U3") (pin "A0") (pinfunction "A0_A0") (pintype "unspecified+no_connect"))
    )
    (net (code "176") (name "unconnected-(U3-PadA1)") (class "Default")
      (node (ref "U3") (pin "A1") (pinfunction "A1_A1") (pintype "unspecified+no_connect"))
    )
    (net (code "177") (name "unconnected-(U3-PadA2)") (class "Default")
      (node (ref "U3") (pin "A2") (pinfunction "A2_A2") (pintype "unspecified+no_connect"))
    )
    (net (code "178") (name "unconnected-(U3-PadRST)") (class "Default")
      (node (ref "U3") (pin "RST") (pinfunction "RST_RST") (pintype "unspecified+no_connect"))
    )
    (net (code "179") (name "unconnected-(U3-PadSC5)") (class "Default")
      (node (ref "U3") (pin "SC5") (pinfunction "SC5_SC5") (pintype "unspecified+no_connect"))
    )
    (net (code "180") (name "unconnected-(U3-PadSC6)") (class "Default")
      (node (ref "U3") (pin "SC6") (pinfunction "SC6_SC6") (pintype "unspecified+no_connect"))
    )
    (net (code "181") (name "unconnected-(U3-PadSD5)") (class "Default")
      (node (ref "U3") (pin "SD5") (pinfunction "SD5_SD5") (pintype "unspecified+no_connect"))
    )
    (net (code "182") (name "unconnected-(U3-PadSD6)") (class "Default")
      (node (ref "U3") (pin "SD6") (pinfunction "SD6_SD6") (pintype "unspecified+no_connect"))
    )
  )
)
